# ES_Daisy_Patch_Rev8.net
KiCad netlist of a schematic drawn in EAGLE
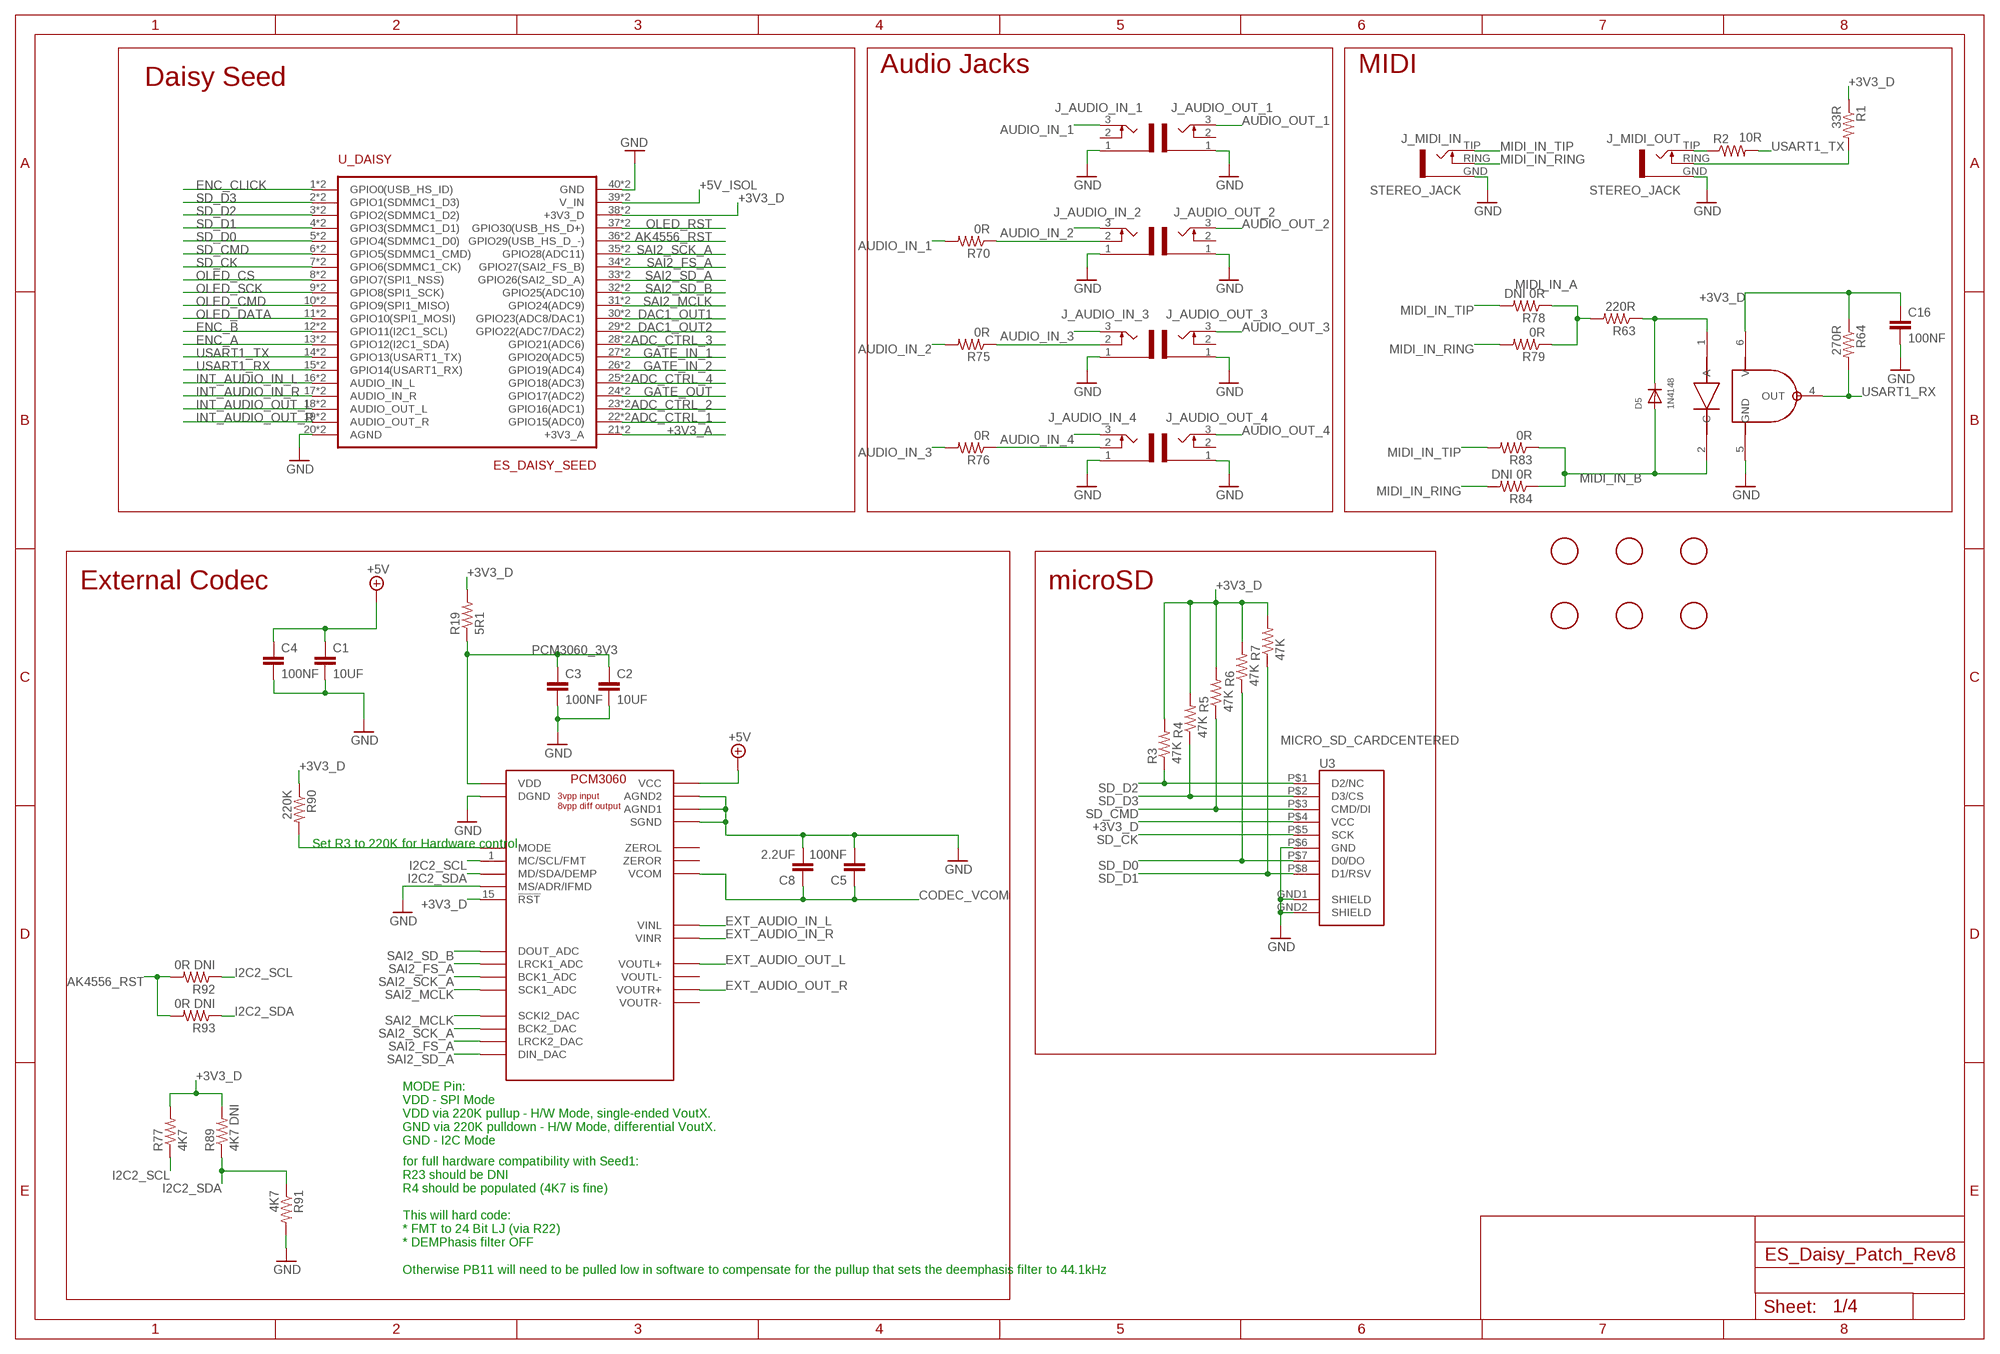
[diagram p0: schematic, sheet 1]
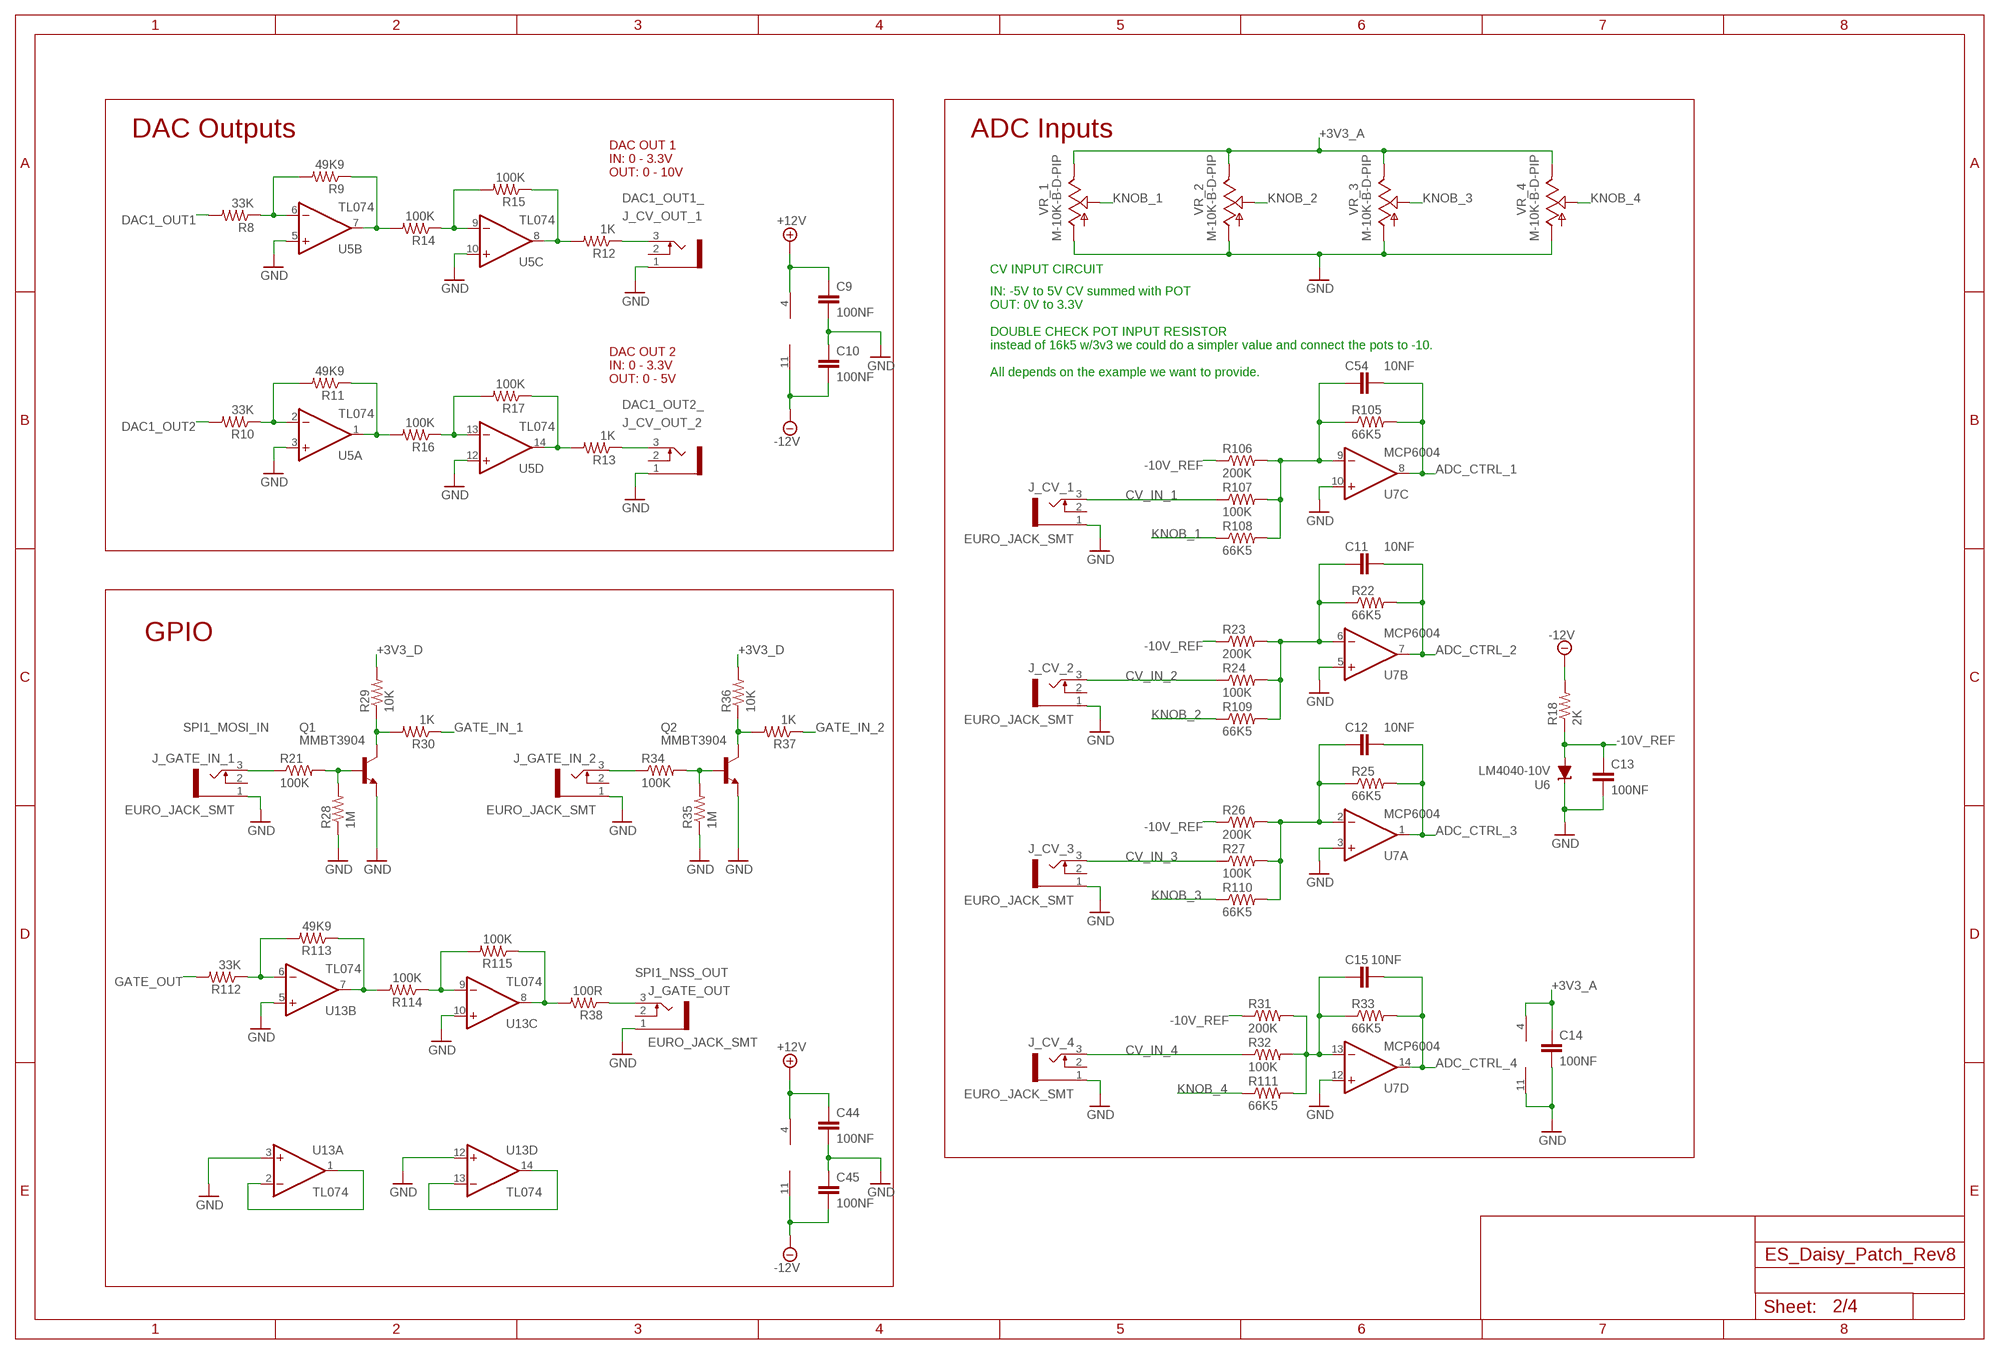
[diagram p1: schematic, sheet 2]
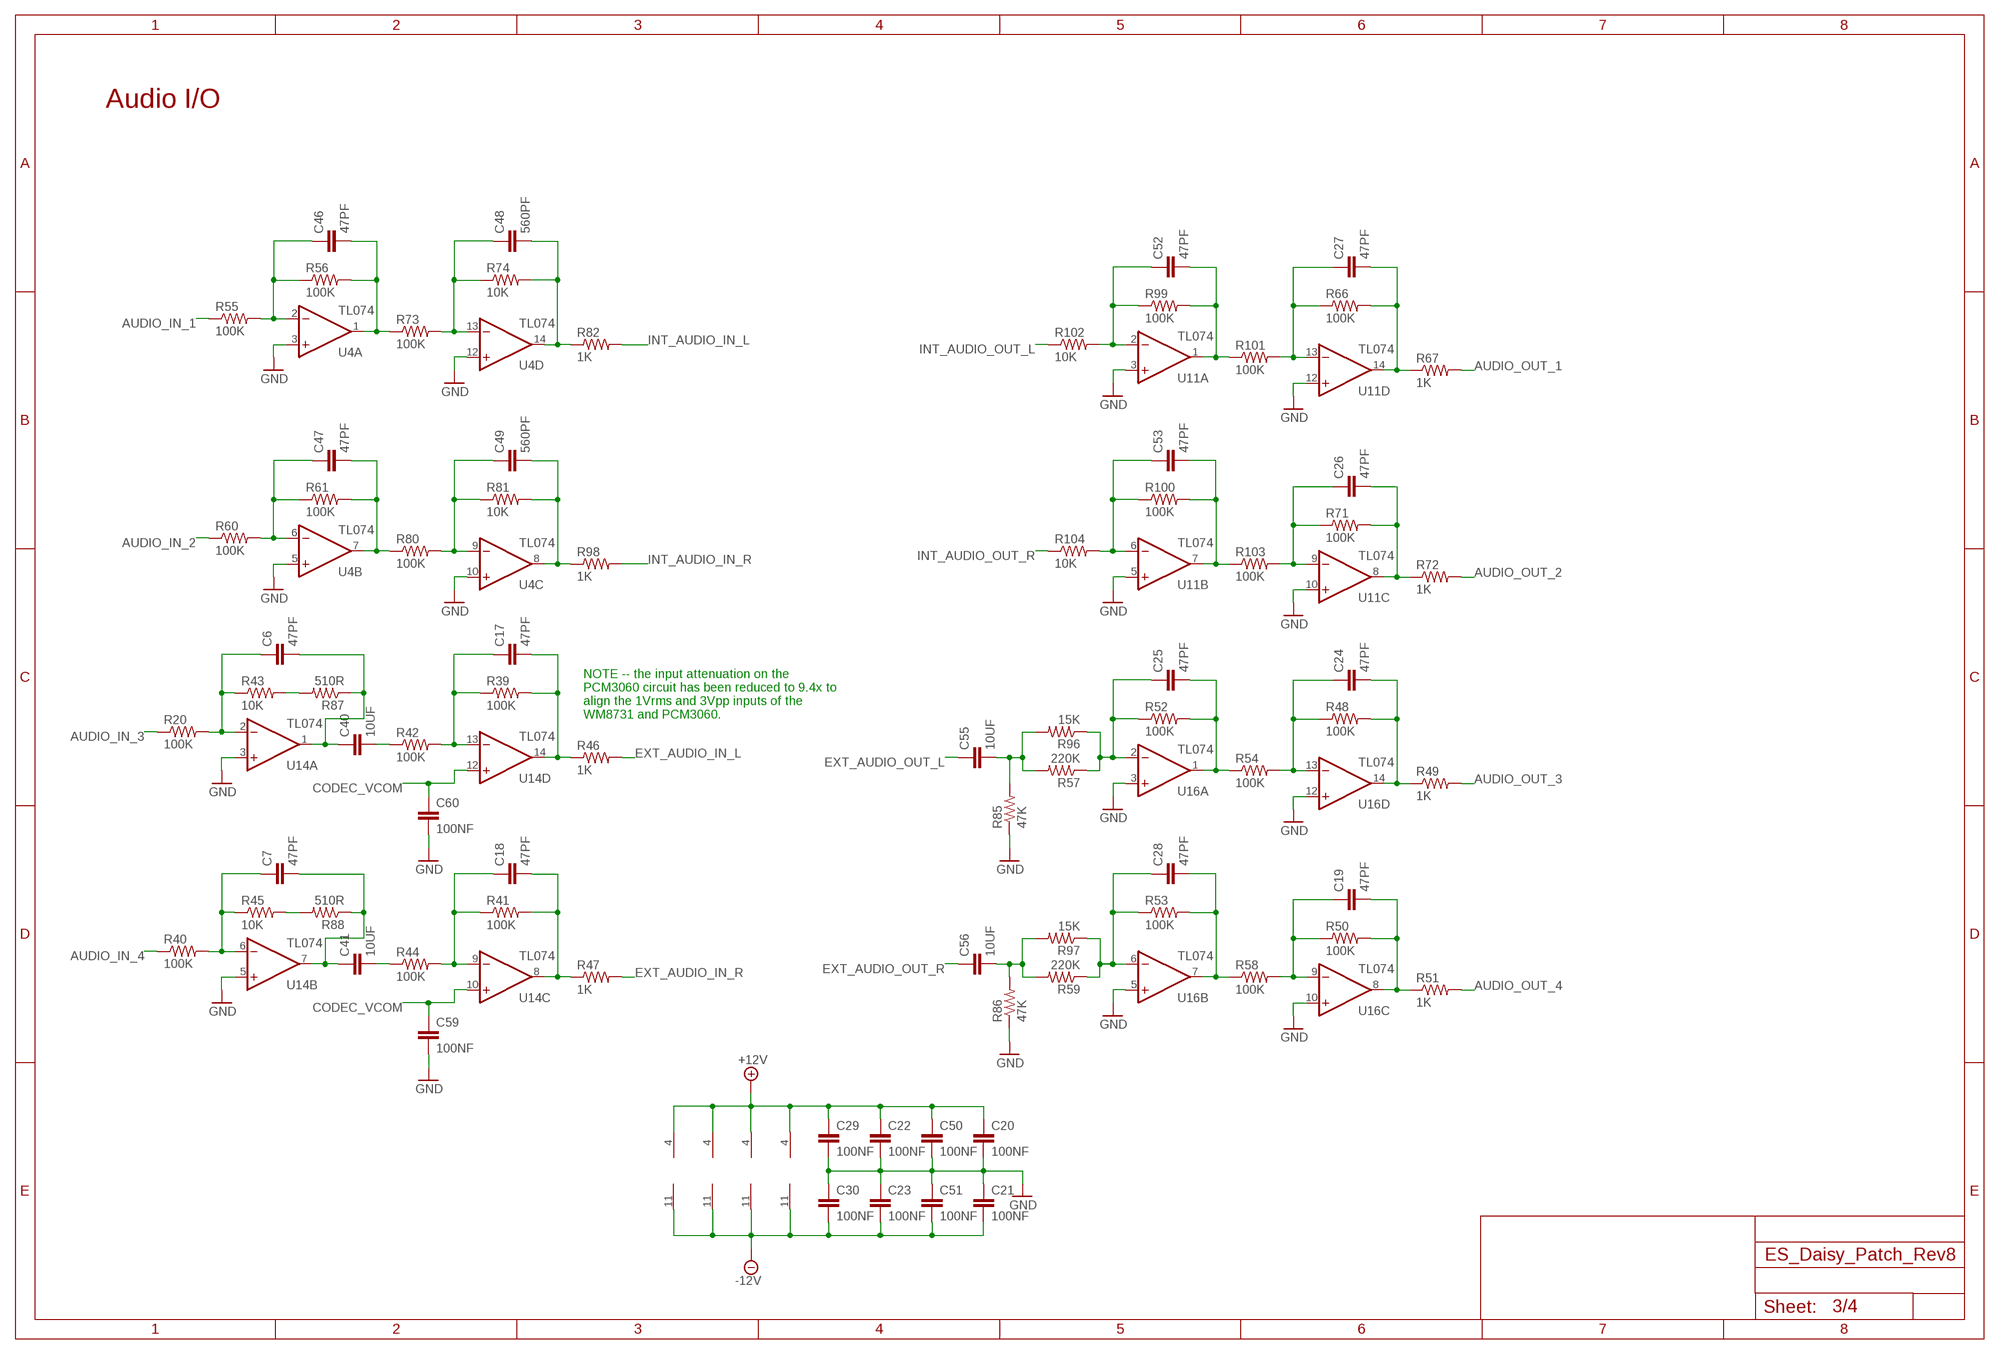
[diagram p2: schematic, sheet 3]
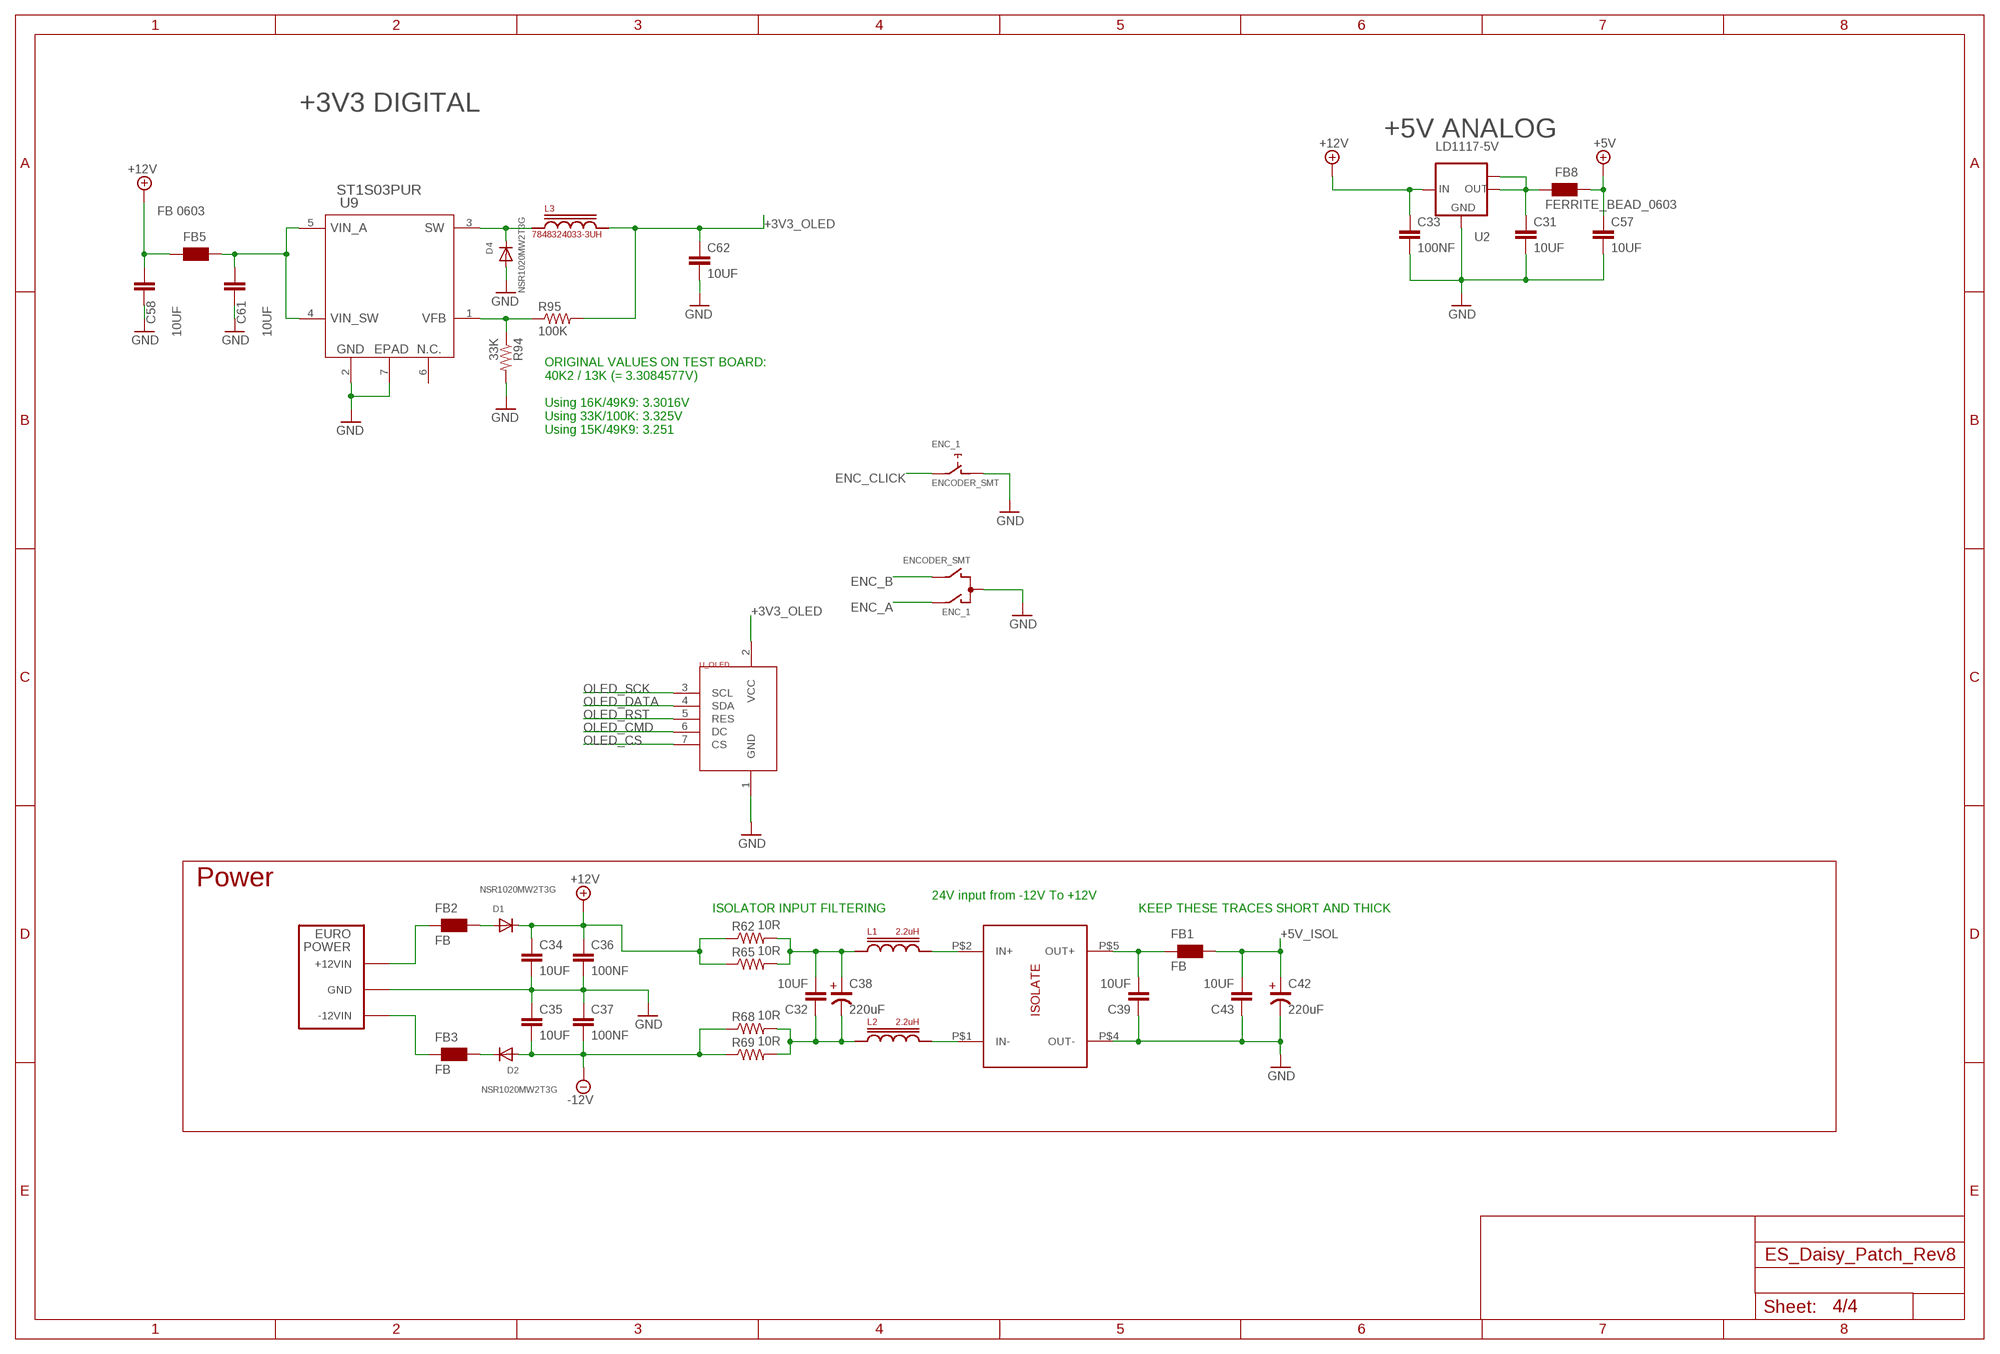
[diagram p3: schematic, sheet 4]

(export (version "E")
  (design (tool "Eeschema 10.0.6"))
  (components
    (comp (ref "C9")
      (value "100NF")
      (footprint "eagle-import:C0402")
      (libsource (lib "eagle-import") (part "C-EUC0402"))
    )
    (comp (ref "C10")
      (value "100NF")
      (footprint "eagle-import:C0402")
      (libsource (lib "eagle-import") (part "C-EUC0402"))
    )
    (comp (ref "C11")
      (value "10NF")
      (footprint "eagle-import:C0603")
      (libsource (lib "eagle-import") (part "C-EUC0603"))
    )
    (comp (ref "C12")
      (value "10NF")
      (footprint "eagle-import:C0603")
      (libsource (lib "eagle-import") (part "C-EUC0603"))
    )
    (comp (ref "C13")
      (value "100NF")
      (footprint "eagle-import:C0402")
      (libsource (lib "eagle-import") (part "C-EUC0402"))
    )
    (comp (ref "C14")
      (value "100NF")
      (footprint "eagle-import:C0402")
      (libsource (lib "eagle-import") (part "C-EUC0402"))
    )
    (comp (ref "C15")
      (value "10NF")
      (footprint "eagle-import:C0603")
      (libsource (lib "eagle-import") (part "C-EUC0603"))
    )
    (comp (ref "C44")
      (value "100NF")
      (footprint "eagle-import:C0402")
      (libsource (lib "eagle-import") (part "C-EUC0402"))
    )
    (comp (ref "C45")
      (value "100NF")
      (footprint "eagle-import:C0402")
      (libsource (lib "eagle-import") (part "C-EUC0402"))
    )
    (comp (ref "C54")
      (value "10NF")
      (footprint "eagle-import:C0603")
      (libsource (lib "eagle-import") (part "C-EUC0603"))
    )
    (comp (ref "J_CV_1")
      (value "EURO_JACK_SMT")
      (footprint "eagle-import:SMT_JACK")
      (libsource (lib "eagle-import") (part "EURO_JACK_SMT"))
    )
    (comp (ref "J_CV_2")
      (value "EURO_JACK_SMT")
      (footprint "eagle-import:SMT_JACK")
      (libsource (lib "eagle-import") (part "EURO_JACK_SMT"))
    )
    (comp (ref "J_CV_3")
      (value "EURO_JACK_SMT")
      (footprint "eagle-import:SMT_JACK")
      (libsource (lib "eagle-import") (part "EURO_JACK_SMT"))
    )
    (comp (ref "J_CV_4")
      (value "EURO_JACK_SMT")
      (footprint "eagle-import:SMT_JACK")
      (libsource (lib "eagle-import") (part "EURO_JACK_SMT"))
    )
    (comp (ref "J_CV_OUT_1")
      (value "EURO_JACK_SMT")
      (footprint "eagle-import:SMT_JACK")
      (libsource (lib "eagle-import") (part "EURO_JACK_SMT"))
    )
    (comp (ref "J_CV_OUT_2")
      (value "EURO_JACK_SMT")
      (footprint "eagle-import:SMT_JACK")
      (libsource (lib "eagle-import") (part "EURO_JACK_SMT"))
    )
    (comp (ref "J_GATE_IN_1")
      (value "EURO_JACK_SMT")
      (footprint "eagle-import:SMT_JACK")
      (libsource (lib "eagle-import") (part "EURO_JACK_SMT"))
    )
    (comp (ref "J_GATE_IN_2")
      (value "EURO_JACK_SMT")
      (footprint "eagle-import:SMT_JACK")
      (libsource (lib "eagle-import") (part "EURO_JACK_SMT"))
    )
    (comp (ref "J_GATE_OUT")
      (value "EURO_JACK_SMT")
      (footprint "eagle-import:SMT_JACK")
      (libsource (lib "eagle-import") (part "EURO_JACK_SMT"))
    )
    (comp (ref "Q1")
      (value "MMBT3904")
      (footprint "eagle-import:SOT23-BEC")
      (libsource (lib "eagle-import") (part "NPNSOT23-BEC"))
    )
    (comp (ref "Q2")
      (value "MMBT3904")
      (footprint "eagle-import:SOT23-BEC")
      (libsource (lib "eagle-import") (part "NPNSOT23-BEC"))
    )
    (comp (ref "R8")
      (value "33K")
      (footprint "eagle-import:R0603")
      (libsource (lib "eagle-import") (part "R-US_R0603"))
    )
    (comp (ref "R9")
      (value "49K9")
      (footprint "eagle-import:R0603")
      (libsource (lib "eagle-import") (part "R-US_R0603"))
    )
    (comp (ref "R10")
      (value "33K")
      (footprint "eagle-import:R0603")
      (libsource (lib "eagle-import") (part "R-US_R0603"))
    )
    (comp (ref "R11")
      (value "49K9")
      (footprint "eagle-import:R0603")
      (libsource (lib "eagle-import") (part "R-US_R0603"))
    )
    (comp (ref "R12")
      (value "1K")
      (footprint "eagle-import:R0402")
      (libsource (lib "eagle-import") (part "R-US_R0402"))
    )
    (comp (ref "R13")
      (value "1K")
      (footprint "eagle-import:R0402")
      (libsource (lib "eagle-import") (part "R-US_R0402"))
    )
    (comp (ref "R14")
      (value "100K")
      (footprint "eagle-import:R0402")
      (libsource (lib "eagle-import") (part "R-US_R0402"))
    )
    (comp (ref "R15")
      (value "100K")
      (footprint "eagle-import:R0402")
      (libsource (lib "eagle-import") (part "R-US_R0402"))
    )
    (comp (ref "R16")
      (value "100K")
      (footprint "eagle-import:R0402")
      (libsource (lib "eagle-import") (part "R-US_R0402"))
    )
    (comp (ref "R17")
      (value "100K")
      (footprint "eagle-import:R0402")
      (libsource (lib "eagle-import") (part "R-US_R0402"))
    )
    (comp (ref "R18")
      (value "2K")
      (footprint "eagle-import:R0603")
      (libsource (lib "eagle-import") (part "R-US_R0603"))
    )
    (comp (ref "R21")
      (value "100K")
      (footprint "eagle-import:R0402")
      (libsource (lib "eagle-import") (part "R-US_R0402"))
    )
    (comp (ref "R22")
      (value "66K5")
      (footprint "eagle-import:R0603")
      (libsource (lib "eagle-import") (part "R-US_R0603"))
    )
    (comp (ref "R23")
      (value "200K")
      (footprint "eagle-import:R0603")
      (libsource (lib "eagle-import") (part "R-US_R0603"))
    )
    (comp (ref "R24")
      (value "100K")
      (footprint "eagle-import:R0402")
      (libsource (lib "eagle-import") (part "R-US_R0402"))
    )
    (comp (ref "R25")
      (value "66K5")
      (footprint "eagle-import:R0603")
      (libsource (lib "eagle-import") (part "R-US_R0603"))
    )
    (comp (ref "R26")
      (value "200K")
      (footprint "eagle-import:R0603")
      (libsource (lib "eagle-import") (part "R-US_R0603"))
    )
    (comp (ref "R27")
      (value "100K")
      (footprint "eagle-import:R0402")
      (libsource (lib "eagle-import") (part "R-US_R0402"))
    )
    (comp (ref "R28")
      (value "1M")
      (footprint "eagle-import:R0603")
      (libsource (lib "eagle-import") (part "R-US_R0603"))
    )
    (comp (ref "R29")
      (value "10K")
      (footprint "eagle-import:R0603")
      (libsource (lib "eagle-import") (part "R-US_R0603"))
    )
    (comp (ref "R30")
      (value "1K")
      (footprint "eagle-import:R0402")
      (libsource (lib "eagle-import") (part "R-US_R0402"))
    )
    (comp (ref "R31")
      (value "200K")
      (footprint "eagle-import:R0603")
      (libsource (lib "eagle-import") (part "R-US_R0603"))
    )
    (comp (ref "R32")
      (value "100K")
      (footprint "eagle-import:R0402")
      (libsource (lib "eagle-import") (part "R-US_R0402"))
    )
    (comp (ref "R33")
      (value "66K5")
      (footprint "eagle-import:R0603")
      (libsource (lib "eagle-import") (part "R-US_R0603"))
    )
    (comp (ref "R34")
      (value "100K")
      (footprint "eagle-import:R0402")
      (libsource (lib "eagle-import") (part "R-US_R0402"))
    )
    (comp (ref "R35")
      (value "1M")
      (footprint "eagle-import:R0603")
      (libsource (lib "eagle-import") (part "R-US_R0603"))
    )
    (comp (ref "R36")
      (value "10K")
      (footprint "eagle-import:R0603")
      (libsource (lib "eagle-import") (part "R-US_R0603"))
    )
    (comp (ref "R37")
      (value "1K")
      (footprint "eagle-import:R0402")
      (libsource (lib "eagle-import") (part "R-US_R0402"))
    )
    (comp (ref "R38")
      (value "100R")
      (footprint "eagle-import:R0603")
      (libsource (lib "eagle-import") (part "R-US_R0603"))
    )
    (comp (ref "R105")
      (value "66K5")
      (footprint "eagle-import:R0603")
      (libsource (lib "eagle-import") (part "R-US_R0603"))
    )
    (comp (ref "R106")
      (value "200K")
      (footprint "eagle-import:R0603")
      (libsource (lib "eagle-import") (part "R-US_R0603"))
    )
    (comp (ref "R107")
      (value "100K")
      (footprint "eagle-import:R0402")
      (libsource (lib "eagle-import") (part "R-US_R0402"))
    )
    (comp (ref "R108")
      (value "66K5")
      (footprint "eagle-import:R0603")
      (libsource (lib "eagle-import") (part "R-US_R0603"))
    )
    (comp (ref "R109")
      (value "66K5")
      (footprint "eagle-import:R0603")
      (libsource (lib "eagle-import") (part "R-US_R0603"))
    )
    (comp (ref "R110")
      (value "66K5")
      (footprint "eagle-import:R0603")
      (libsource (lib "eagle-import") (part "R-US_R0603"))
    )
    (comp (ref "R111")
      (value "66K5")
      (footprint "eagle-import:R0603")
      (libsource (lib "eagle-import") (part "R-US_R0603"))
    )
    (comp (ref "R112")
      (value "33K")
      (footprint "eagle-import:R0603")
      (libsource (lib "eagle-import") (part "R-US_R0603"))
    )
    (comp (ref "R113")
      (value "49K9")
      (footprint "eagle-import:R0603")
      (libsource (lib "eagle-import") (part "R-US_R0603"))
    )
    (comp (ref "R114")
      (value "100K")
      (footprint "eagle-import:R0402")
      (libsource (lib "eagle-import") (part "R-US_R0402"))
    )
    (comp (ref "R115")
      (value "100K")
      (footprint "eagle-import:R0402")
      (libsource (lib "eagle-import") (part "R-US_R0402"))
    )
    (comp (ref "U5")
      (value "TL074")
      (footprint "eagle-import:TSSOP-14")
      (fields (field (name "MPN") "TL074CPWR"))
      (libsource (lib "eagle-import") (part "TL074_TSSOP-14"))
    )
    (comp (ref "U6")
      (value "LM4040-10V")
      (footprint "eagle-import:DBZ_R-PDSO-G3")
      (fields (field (name "MPN") "LM4041A12IDBZR"))
      (libsource (lib "eagle-import") (part "LM4040-10VDBZA12"))
    )
    (comp (ref "U7")
      (value "MCP6004")
      (footprint "eagle-import:TSSOP-14")
      (fields (field (name "MPN") "MCP6004T-E/ST"))
      (libsource (lib "eagle-import") (part "MCP6004_TSSOP-14"))
    )
    (comp (ref "U13")
      (value "TL074")
      (footprint "eagle-import:TSSOP-14")
      (fields (field (name "MPN") "TL074CPWR"))
      (libsource (lib "eagle-import") (part "TL074_TSSOP-14"))
    )
    (comp (ref "VR_1")
      (value "M-10K-B-D-PIP")
      (footprint "eagle-import:PIP_POT_PASTE6")
      (libsource (lib "eagle-import") (part "POT_9MM_SNAP-IN__PIPC6"))
    )
    (comp (ref "VR_2")
      (value "M-10K-B-D-PIP")
      (footprint "eagle-import:PIP_POT_PASTE6")
      (libsource (lib "eagle-import") (part "POT_9MM_SNAP-IN__PIPC6"))
    )
    (comp (ref "VR_3")
      (value "M-10K-B-D-PIP")
      (footprint "eagle-import:PIP_POT_PASTE6")
      (libsource (lib "eagle-import") (part "POT_9MM_SNAP-IN__PIPC6"))
    )
    (comp (ref "VR_4")
      (value "M-10K-B-D-PIP")
      (footprint "eagle-import:PIP_POT_PASTE6")
      (libsource (lib "eagle-import") (part "POT_9MM_SNAP-IN__PIPC6"))
    )
    (comp (ref "C6")
      (value "47PF")
      (footprint "eagle-import:C0603")
      (libsource (lib "eagle-import") (part "C-EUC0603"))
    )
    (comp (ref "C7")
      (value "47PF")
      (footprint "eagle-import:C0603")
      (libsource (lib "eagle-import") (part "C-EUC0603"))
    )
    (comp (ref "C17")
      (value "47PF")
      (footprint "eagle-import:C0603")
      (libsource (lib "eagle-import") (part "C-EUC0603"))
    )
    (comp (ref "C18")
      (value "47PF")
      (footprint "eagle-import:C0603")
      (libsource (lib "eagle-import") (part "C-EUC0603"))
    )
    (comp (ref "C19")
      (value "47PF")
      (footprint "eagle-import:C0603")
      (libsource (lib "eagle-import") (part "C-EUC0603"))
    )
    (comp (ref "C20")
      (value "100NF")
      (footprint "eagle-import:C0402")
      (libsource (lib "eagle-import") (part "C-EUC0402"))
    )
    (comp (ref "C21")
      (value "100NF")
      (footprint "eagle-import:C0402")
      (libsource (lib "eagle-import") (part "C-EUC0402"))
    )
    (comp (ref "C22")
      (value "100NF")
      (footprint "eagle-import:C0402")
      (libsource (lib "eagle-import") (part "C-EUC0402"))
    )
    (comp (ref "C23")
      (value "100NF")
      (footprint "eagle-import:C0402")
      (libsource (lib "eagle-import") (part "C-EUC0402"))
    )
    (comp (ref "C24")
      (value "47PF")
      (footprint "eagle-import:C0603")
      (libsource (lib "eagle-import") (part "C-EUC0603"))
    )
    (comp (ref "C25")
      (value "47PF")
      (footprint "eagle-import:C0603")
      (libsource (lib "eagle-import") (part "C-EUC0603"))
    )
    (comp (ref "C26")
      (value "47PF")
      (footprint "eagle-import:C0603")
      (libsource (lib "eagle-import") (part "C-EUC0603"))
    )
    (comp (ref "C27")
      (value "47PF")
      (footprint "eagle-import:C0603")
      (libsource (lib "eagle-import") (part "C-EUC0603"))
    )
    (comp (ref "C28")
      (value "47PF")
      (footprint "eagle-import:C0603")
      (libsource (lib "eagle-import") (part "C-EUC0603"))
    )
    (comp (ref "C29")
      (value "100NF")
      (footprint "eagle-import:C0402")
      (libsource (lib "eagle-import") (part "C-EUC0402"))
    )
    (comp (ref "C30")
      (value "100NF")
      (footprint "eagle-import:C0402")
      (libsource (lib "eagle-import") (part "C-EUC0402"))
    )
    (comp (ref "C40")
      (value "10UF")
      (footprint "eagle-import:C0805")
      (libsource (lib "eagle-import") (part "C-EUC0805"))
    )
    (comp (ref "C41")
      (value "10UF")
      (footprint "eagle-import:C0805")
      (libsource (lib "eagle-import") (part "C-EUC0805"))
    )
    (comp (ref "C46")
      (value "47PF")
      (footprint "eagle-import:C0603")
      (libsource (lib "eagle-import") (part "C-EUC0603"))
    )
    (comp (ref "C47")
      (value "47PF")
      (footprint "eagle-import:C0603")
      (libsource (lib "eagle-import") (part "C-EUC0603"))
    )
    (comp (ref "C48")
      (value "560PF")
      (footprint "eagle-import:C0603")
      (libsource (lib "eagle-import") (part "C-EUC0603"))
    )
    (comp (ref "C49")
      (value "560PF")
      (footprint "eagle-import:C0603")
      (libsource (lib "eagle-import") (part "C-EUC0603"))
    )
    (comp (ref "C50")
      (value "100NF")
      (footprint "eagle-import:C0402")
      (libsource (lib "eagle-import") (part "C-EUC0402"))
    )
    (comp (ref "C51")
      (value "100NF")
      (footprint "eagle-import:C0402")
      (libsource (lib "eagle-import") (part "C-EUC0402"))
    )
    (comp (ref "C52")
      (value "47PF")
      (footprint "eagle-import:C0603")
      (libsource (lib "eagle-import") (part "C-EUC0603"))
    )
    (comp (ref "C53")
      (value "47PF")
      (footprint "eagle-import:C0603")
      (libsource (lib "eagle-import") (part "C-EUC0603"))
    )
    (comp (ref "C55")
      (value "10UF")
      (footprint "eagle-import:C0805")
      (libsource (lib "eagle-import") (part "C-EUC0805"))
    )
    (comp (ref "C56")
      (value "10UF")
      (footprint "eagle-import:C0805")
      (libsource (lib "eagle-import") (part "C-EUC0805"))
    )
    (comp (ref "C59")
      (value "100NF")
      (footprint "eagle-import:C0402")
      (libsource (lib "eagle-import") (part "C-EUC0402"))
    )
    (comp (ref "C60")
      (value "100NF")
      (footprint "eagle-import:C0402")
      (libsource (lib "eagle-import") (part "C-EUC0402"))
    )
    (comp (ref "R20")
      (value "100K")
      (footprint "eagle-import:R0402")
      (libsource (lib "eagle-import") (part "R-US_R0402"))
    )
    (comp (ref "R39")
      (value "100K")
      (footprint "eagle-import:R0402")
      (libsource (lib "eagle-import") (part "R-US_R0402"))
    )
    (comp (ref "R40")
      (value "100K")
      (footprint "eagle-import:R0402")
      (libsource (lib "eagle-import") (part "R-US_R0402"))
    )
    (comp (ref "R41")
      (value "100K")
      (footprint "eagle-import:R0402")
      (libsource (lib "eagle-import") (part "R-US_R0402"))
    )
    (comp (ref "R42")
      (value "100K")
      (footprint "eagle-import:R0402")
      (libsource (lib "eagle-import") (part "R-US_R0402"))
    )
    (comp (ref "R43")
      (value "10K")
      (footprint "eagle-import:R0603")
      (libsource (lib "eagle-import") (part "R-US_R0603"))
    )
    (comp (ref "R44")
      (value "100K")
      (footprint "eagle-import:R0402")
      (libsource (lib "eagle-import") (part "R-US_R0402"))
    )
    (comp (ref "R45")
      (value "10K")
      (footprint "eagle-import:R0603")
      (libsource (lib "eagle-import") (part "R-US_R0603"))
    )
    (comp (ref "R46")
      (value "1K")
      (footprint "eagle-import:R0402")
      (libsource (lib "eagle-import") (part "R-US_R0402"))
    )
    (comp (ref "R47")
      (value "1K")
      (footprint "eagle-import:R0402")
      (libsource (lib "eagle-import") (part "R-US_R0402"))
    )
    (comp (ref "R48")
      (value "100K")
      (footprint "eagle-import:R0402")
      (libsource (lib "eagle-import") (part "R-US_R0402"))
    )
    (comp (ref "R49")
      (value "1K")
      (footprint "eagle-import:R0402")
      (libsource (lib "eagle-import") (part "R-US_R0402"))
    )
    (comp (ref "R50")
      (value "100K")
      (footprint "eagle-import:R0402")
      (libsource (lib "eagle-import") (part "R-US_R0402"))
    )
    (comp (ref "R51")
      (value "1K")
      (footprint "eagle-import:R0402")
      (libsource (lib "eagle-import") (part "R-US_R0402"))
    )
    (comp (ref "R52")
      (value "100K")
      (footprint "eagle-import:R0402")
      (libsource (lib "eagle-import") (part "R-US_R0402"))
    )
    (comp (ref "R53")
      (value "100K")
      (footprint "eagle-import:R0402")
      (libsource (lib "eagle-import") (part "R-US_R0402"))
    )
    (comp (ref "R54")
      (value "100K")
      (footprint "eagle-import:R0402")
      (libsource (lib "eagle-import") (part "R-US_R0402"))
    )
    (comp (ref "R55")
      (value "100K")
      (footprint "eagle-import:R0402")
      (libsource (lib "eagle-import") (part "R-US_R0402"))
    )
    (comp (ref "R56")
      (value "100K")
      (footprint "eagle-import:R0402")
      (libsource (lib "eagle-import") (part "R-US_R0402"))
    )
    (comp (ref "R57")
      (value "220K")
      (footprint "eagle-import:R0603")
      (libsource (lib "eagle-import") (part "R-US_R0603"))
    )
    (comp (ref "R58")
      (value "100K")
      (footprint "eagle-import:R0402")
      (libsource (lib "eagle-import") (part "R-US_R0402"))
    )
    (comp (ref "R59")
      (value "220K")
      (footprint "eagle-import:R0603")
      (libsource (lib "eagle-import") (part "R-US_R0603"))
    )
    (comp (ref "R60")
      (value "100K")
      (footprint "eagle-import:R0402")
      (libsource (lib "eagle-import") (part "R-US_R0402"))
    )
    (comp (ref "R61")
      (value "100K")
      (footprint "eagle-import:R0402")
      (libsource (lib "eagle-import") (part "R-US_R0402"))
    )
    (comp (ref "R66")
      (value "100K")
      (footprint "eagle-import:R0402")
      (libsource (lib "eagle-import") (part "R-US_R0402"))
    )
    (comp (ref "R67")
      (value "1K")
      (footprint "eagle-import:R0402")
      (libsource (lib "eagle-import") (part "R-US_R0402"))
    )
    (comp (ref "R71")
      (value "100K")
      (footprint "eagle-import:R0402")
      (libsource (lib "eagle-import") (part "R-US_R0402"))
    )
    (comp (ref "R72")
      (value "1K")
      (footprint "eagle-import:R0402")
      (libsource (lib "eagle-import") (part "R-US_R0402"))
    )
    (comp (ref "R73")
      (value "100K")
      (footprint "eagle-import:R0402")
      (libsource (lib "eagle-import") (part "R-US_R0402"))
    )
    (comp (ref "R74")
      (value "10K")
      (footprint "eagle-import:R0603")
      (libsource (lib "eagle-import") (part "R-US_R0603"))
    )
    (comp (ref "R80")
      (value "100K")
      (footprint "eagle-import:R0402")
      (libsource (lib "eagle-import") (part "R-US_R0402"))
    )
    (comp (ref "R81")
      (value "10K")
      (footprint "eagle-import:R0603")
      (libsource (lib "eagle-import") (part "R-US_R0603"))
    )
    (comp (ref "R82")
      (value "1K")
      (footprint "eagle-import:R0402")
      (libsource (lib "eagle-import") (part "R-US_R0402"))
    )
    (comp (ref "R85")
      (value "47K")
      (footprint "eagle-import:R0603")
      (libsource (lib "eagle-import") (part "R-US_R0603"))
    )
    (comp (ref "R86")
      (value "47K")
      (footprint "eagle-import:R0603")
      (libsource (lib "eagle-import") (part "R-US_R0603"))
    )
    (comp (ref "R87")
      (value "510R")
      (footprint "eagle-import:R0603")
      (libsource (lib "eagle-import") (part "R-US_R0603"))
    )
    (comp (ref "R88")
      (value "510R")
      (footprint "eagle-import:R0603")
      (libsource (lib "eagle-import") (part "R-US_R0603"))
    )
    (comp (ref "R96")
      (value "15K")
      (footprint "eagle-import:R0603")
      (libsource (lib "eagle-import") (part "R-US_R0603"))
    )
    (comp (ref "R97")
      (value "15K")
      (footprint "eagle-import:R0603")
      (libsource (lib "eagle-import") (part "R-US_R0603"))
    )
    (comp (ref "R98")
      (value "1K")
      (footprint "eagle-import:R0402")
      (libsource (lib "eagle-import") (part "R-US_R0402"))
    )
    (comp (ref "R99")
      (value "100K")
      (footprint "eagle-import:R0402")
      (libsource (lib "eagle-import") (part "R-US_R0402"))
    )
    (comp (ref "R100")
      (value "100K")
      (footprint "eagle-import:R0402")
      (libsource (lib "eagle-import") (part "R-US_R0402"))
    )
    (comp (ref "R101")
      (value "100K")
      (footprint "eagle-import:R0402")
      (libsource (lib "eagle-import") (part "R-US_R0402"))
    )
    (comp (ref "R102")
      (value "10K")
      (footprint "eagle-import:R0603")
      (libsource (lib "eagle-import") (part "R-US_R0603"))
    )
    (comp (ref "R103")
      (value "100K")
      (footprint "eagle-import:R0402")
      (libsource (lib "eagle-import") (part "R-US_R0402"))
    )
    (comp (ref "R104")
      (value "10K")
      (footprint "eagle-import:R0603")
      (libsource (lib "eagle-import") (part "R-US_R0603"))
    )
    (comp (ref "U4")
      (value "TL074")
      (footprint "eagle-import:TSSOP-14")
      (fields (field (name "MPN") "TL074CPWR"))
      (libsource (lib "eagle-import") (part "TL074_TSSOP-14"))
    )
    (comp (ref "U11")
      (value "TL074")
      (footprint "eagle-import:TSSOP-14")
      (fields (field (name "MPN") "TL074CPWR"))
      (libsource (lib "eagle-import") (part "TL074_TSSOP-14"))
    )
    (comp (ref "U14")
      (value "TL074")
      (footprint "eagle-import:TSSOP-14")
      (fields (field (name "MPN") "TL074CPWR"))
      (libsource (lib "eagle-import") (part "TL074_TSSOP-14"))
    )
    (comp (ref "U16")
      (value "TL074")
      (footprint "eagle-import:TSSOP-14")
      (fields (field (name "MPN") "TL074CPWR"))
      (libsource (lib "eagle-import") (part "TL074_TSSOP-14"))
    )
    (comp (ref "C31")
      (value "10UF")
      (footprint "eagle-import:C0805")
      (libsource (lib "eagle-import") (part "C-EUC0805"))
    )
    (comp (ref "C32")
      (value "10UF")
      (footprint "eagle-import:C0805")
      (libsource (lib "eagle-import") (part "C-EUC0805"))
    )
    (comp (ref "C33")
      (value "100NF")
      (footprint "eagle-import:C0402")
      (libsource (lib "eagle-import") (part "C-EUC0402"))
    )
    (comp (ref "C34")
      (value "10UF")
      (footprint "eagle-import:C0805")
      (libsource (lib "eagle-import") (part "C-EUC0805"))
    )
    (comp (ref "C35")
      (value "10UF")
      (footprint "eagle-import:C0805")
      (libsource (lib "eagle-import") (part "C-EUC0805"))
    )
    (comp (ref "C36")
      (value "100NF")
      (footprint "eagle-import:C0402")
      (libsource (lib "eagle-import") (part "C-EUC0402"))
    )
    (comp (ref "C37")
      (value "100NF")
      (footprint "eagle-import:C0402")
      (libsource (lib "eagle-import") (part "C-EUC0402"))
    )
    (comp (ref "C38")
      (value "220uF")
      (footprint "eagle-import:PANASONIC_D")
      (libsource (lib "eagle-import") (part "C-EU-POL_D"))
    )
    (comp (ref "C39")
      (value "10UF")
      (footprint "eagle-import:C0805")
      (libsource (lib "eagle-import") (part "C-EUC0805"))
    )
    (comp (ref "C42")
      (value "220uF")
      (footprint "eagle-import:PANASONIC_D")
      (libsource (lib "eagle-import") (part "C-EU-POL_D"))
    )
    (comp (ref "C43")
      (value "10UF")
      (footprint "eagle-import:C0805")
      (libsource (lib "eagle-import") (part "C-EUC0805"))
    )
    (comp (ref "C57")
      (value "10UF")
      (footprint "eagle-import:C0805")
      (libsource (lib "eagle-import") (part "C-EUC0805"))
    )
    (comp (ref "C58")
      (value "10UF")
      (footprint "eagle-import:C0805")
      (libsource (lib "eagle-import") (part "C-EUC0805"))
    )
    (comp (ref "C61")
      (value "10UF")
      (footprint "eagle-import:C0805")
      (libsource (lib "eagle-import") (part "Electrosmith-Passives_29888544_C-EUC0805"))
    )
    (comp (ref "C62")
      (value "10UF")
      (footprint "eagle-import:C0805")
      (libsource (lib "eagle-import") (part "C-EUC0805"))
    )
    (comp (ref "D1")
      (value "NSR1020MW2T3G")
      (footprint "eagle-import:SOD-323F")
      (libsource (lib "eagle-import") (part "DIODE_SOD-323F"))
    )
    (comp (ref "D2")
      (value "NSR1020MW2T3G")
      (footprint "eagle-import:SOD-323F")
      (libsource (lib "eagle-import") (part "DIODE_SOD-323F"))
    )
    (comp (ref "D4")
      (value "NSR1020MW2T3G")
      (footprint "eagle-import:SOD-323F")
      (libsource (lib "eagle-import") (part "Electrosmith-Semiconductors_29887508_DIODE_SOD-323F"))
    )
    (comp (ref "ENC_1")
      (value "ENCODER_SMT")
      (footprint "eagle-import:VH1-147")
      (libsource (lib "eagle-import") (part "ENCODER_SMT"))
    )
    (comp (ref "EP1")
      (value "EURORACK_POWERSMT_2X8")
      (footprint "eagle-import:2X8_SMD_PWR")
      (libsource (lib "eagle-import") (part "EURORACK_POWERSMT_2X8"))
    )
    (comp (ref "FB1")
      (value "FB")
      (footprint "eagle-import:WUERTH-ELEKTRONIK_0603")
      (fields (field (name "MPN") "MI0603J601R-10"))
      (libsource (lib "eagle-import") (part "FERRITE_BEAD_0603"))
    )
    (comp (ref "FB2")
      (value "FB")
      (footprint "eagle-import:WUERTH-ELEKTRONIK_0603")
      (fields (field (name "MPN") "MI0603J601R-10"))
      (libsource (lib "eagle-import") (part "FERRITE_BEAD_0603"))
    )
    (comp (ref "FB3")
      (value "FB")
      (footprint "eagle-import:WUERTH-ELEKTRONIK_0603")
      (fields (field (name "MPN") "MI0603J601R-10"))
      (libsource (lib "eagle-import") (part "FERRITE_BEAD_0603"))
    )
    (comp (ref "FB5")
      (value "FB 0603")
      (footprint "eagle-import:WUERTH-ELEKTRONIK_0603")
      (fields (field (name "MPN") "MI0603J601R-10"))
      (libsource (lib "eagle-import") (part "FERRITE_BEAD_0603"))
    )
    (comp (ref "FB8")
      (value "FERRITE_BEAD_0603")
      (footprint "eagle-import:WUERTH-ELEKTRONIK_0603")
      (fields (field (name "MPN") "MI0603J601R-10"))
      (libsource (lib "eagle-import") (part "FERRITE_BEAD_0603"))
    )
    (comp (ref "L1")
      (value "2.2uH")
      (footprint "eagle-import:BOURNS_SRP2010")
      (libsource (lib "eagle-import") (part "INDUCTORS"))
    )
    (comp (ref "L2")
      (value "2.2uH")
      (footprint "eagle-import:BOURNS_SRP2010")
      (libsource (lib "eagle-import") (part "INDUCTORS"))
    )
    (comp (ref "L3")
      (value "7848324033-3UH")
      (footprint "eagle-import:I1008")
      (fields (field (name "MPN") "AIML-1008HC-3R3M-T"))
      (libsource (lib "eagle-import") (part "INDUCTOR1008"))
    )
    (comp (ref "R62")
      (value "10R")
      (footprint "eagle-import:R0603")
      (libsource (lib "eagle-import") (part "R-US_R0603"))
    )
    (comp (ref "R65")
      (value "10R")
      (footprint "eagle-import:R0603")
      (libsource (lib "eagle-import") (part "R-US_R0603"))
    )
    (comp (ref "R68")
      (value "10R")
      (footprint "eagle-import:R0603")
      (libsource (lib "eagle-import") (part "R-US_R0603"))
    )
    (comp (ref "R69")
      (value "10R")
      (footprint "eagle-import:R0603")
      (libsource (lib "eagle-import") (part "R-US_R0603"))
    )
    (comp (ref "R94")
      (value "33K")
      (footprint "eagle-import:R0603")
      (libsource (lib "eagle-import") (part "R-US_R0603"))
    )
    (comp (ref "R95")
      (value "100K")
      (footprint "eagle-import:R0402")
      (libsource (lib "eagle-import") (part "R-US_R0402"))
    )
    (comp (ref "U$1")
      (value "U24V/5V DC/DC ISOLATOR")
      (footprint "eagle-import:XP_POWER_ISEXXXXA")
      (fields (field (name "MPN") "ISE2405A"))
      (libsource (lib "eagle-import") (part "POWER_ISOLATE"))
    )
    (comp (ref "U2")
      (value "LD1117-5V")
      (footprint "eagle-import:SOT223")
      (fields (field (name "MPN") "LD1117S50CTR"))
      (libsource (lib "eagle-import") (part "LD1117-5V"))
    )
    (comp (ref "U9")
      (value "ST1S03PUR")
      (footprint "eagle-import:DFN06_3X3_STM")
      (fields (field (name "COPYRIGHT") "Copyright (C) 2021 Ultra Librarian. All rights reserved."))
      (libsource (lib "eagle-import") (part "ST1S03PUR"))
    )
    (comp (ref "U_OLED")
      (value "OLED_DISPLAY")
      (footprint "eagle-import:ER-OLEDM015-2")
      (fields (field (name "MPN") "ER-OLEDM015-2W-SPI-I2C"))
      (libsource (lib "eagle-import") (part "OLED_DISPLAY"))
    )
    (comp (ref "C1")
      (value "10UF")
      (footprint "eagle-import:C0805")
      (libsource (lib "eagle-import") (part "C-EUC0805"))
    )
    (comp (ref "C2")
      (value "10UF")
      (footprint "eagle-import:C0805")
      (libsource (lib "eagle-import") (part "C-EUC0805"))
    )
    (comp (ref "C3")
      (value "100NF")
      (footprint "eagle-import:C0402")
      (libsource (lib "eagle-import") (part "C-EUC0402"))
    )
    (comp (ref "C4")
      (value "100NF")
      (footprint "eagle-import:C0402")
      (libsource (lib "eagle-import") (part "C-EUC0402"))
    )
    (comp (ref "C5")
      (value "100NF")
      (footprint "eagle-import:C0402")
      (libsource (lib "eagle-import") (part "C-EUC0402"))
    )
    (comp (ref "C8")
      (value "2.2UF")
      (footprint "eagle-import:C0603")
      (libsource (lib "eagle-import") (part "C-EUC0603"))
    )
    (comp (ref "C16")
      (value "100NF")
      (footprint "eagle-import:C0402")
      (libsource (lib "eagle-import") (part "C-EUC0402"))
    )
    (comp (ref "D5")
      (value "1N4148")
      (footprint "eagle-import:SOD-323F")
      (libsource (lib "eagle-import") (part "DIODE_SOD-323F"))
    )
    (comp (ref "FD1")
      (value "FIDUCIAL")
      (footprint "eagle-import:FIDUCIAL_1MM")
      (libsource (lib "eagle-import") (part "FIDUCIAL"))
    )
    (comp (ref "FD2")
      (value "FIDUCIAL")
      (footprint "eagle-import:FIDUCIAL_1MM")
      (libsource (lib "eagle-import") (part "FIDUCIAL"))
    )
    (comp (ref "FD3")
      (value "FIDUCIAL")
      (footprint "eagle-import:FIDUCIAL_1MM")
      (libsource (lib "eagle-import") (part "FIDUCIAL"))
    )
    (comp (ref "FD4")
      (value "FIDUCIAL")
      (footprint "eagle-import:FIDUCIAL_1MM")
      (libsource (lib "eagle-import") (part "FIDUCIAL"))
    )
    (comp (ref "FD5")
      (value "FIDUCIAL")
      (footprint "eagle-import:FIDUCIAL_1MM")
      (libsource (lib "eagle-import") (part "FIDUCIAL"))
    )
    (comp (ref "FD6")
      (value "FIDUCIAL")
      (footprint "eagle-import:FIDUCIAL_1MM")
      (libsource (lib "eagle-import") (part "FIDUCIAL"))
    )
    (comp (ref "J_AUDIO_IN_1")
      (value "EURO_JACK_SMT")
      (footprint "eagle-import:SMT_JACK")
      (libsource (lib "eagle-import") (part "EURO_JACK_SMT"))
    )
    (comp (ref "J_AUDIO_IN_2")
      (value "EURO_JACK_SMT")
      (footprint "eagle-import:SMT_JACK")
      (libsource (lib "eagle-import") (part "EURO_JACK_SMT"))
    )
    (comp (ref "J_AUDIO_IN_3")
      (value "EURO_JACK_SMT")
      (footprint "eagle-import:SMT_JACK")
      (libsource (lib "eagle-import") (part "EURO_JACK_SMT"))
    )
    (comp (ref "J_AUDIO_IN_4")
      (value "EURO_JACK_SMT")
      (footprint "eagle-import:SMT_JACK")
      (libsource (lib "eagle-import") (part "EURO_JACK_SMT"))
    )
    (comp (ref "J_AUDIO_OUT_1")
      (value "EURO_JACK_SMT")
      (footprint "eagle-import:SMT_JACK")
      (libsource (lib "eagle-import") (part "EURO_JACK_SMT"))
    )
    (comp (ref "J_AUDIO_OUT_2")
      (value "EURO_JACK_SMT")
      (footprint "eagle-import:SMT_JACK")
      (libsource (lib "eagle-import") (part "EURO_JACK_SMT"))
    )
    (comp (ref "J_AUDIO_OUT_3")
      (value "EURO_JACK_SMT")
      (footprint "eagle-import:SMT_JACK")
      (libsource (lib "eagle-import") (part "EURO_JACK_SMT"))
    )
    (comp (ref "J_AUDIO_OUT_4")
      (value "EURO_JACK_SMT")
      (footprint "eagle-import:SMT_JACK")
      (libsource (lib "eagle-import") (part "EURO_JACK_SMT"))
    )
    (comp (ref "J_MIDI_IN")
      (value "STEREO_JACK")
      (footprint "eagle-import:STEREO_JACK_3.5MM")
      (libsource (lib "eagle-import") (part "STEREO_JACK"))
    )
    (comp (ref "J_MIDI_OUT")
      (value "STEREO_JACK")
      (footprint "eagle-import:STEREO_JACK_3.5MM")
      (libsource (lib "eagle-import") (part "STEREO_JACK"))
    )
    (comp (ref "R1")
      (value "33R")
      (footprint "eagle-import:R0603")
      (libsource (lib "eagle-import") (part "R-US_R0603"))
    )
    (comp (ref "R2")
      (value "10R")
      (footprint "eagle-import:R0603")
      (libsource (lib "eagle-import") (part "R-US_R0603"))
    )
    (comp (ref "R3")
      (value "47K")
      (footprint "eagle-import:R0603")
      (libsource (lib "eagle-import") (part "R-US_R0603"))
    )
    (comp (ref "R4")
      (value "47K")
      (footprint "eagle-import:R0603")
      (libsource (lib "eagle-import") (part "R-US_R0603"))
    )
    (comp (ref "R5")
      (value "47K")
      (footprint "eagle-import:R0603")
      (libsource (lib "eagle-import") (part "R-US_R0603"))
    )
    (comp (ref "R6")
      (value "47K")
      (footprint "eagle-import:R0603")
      (libsource (lib "eagle-import") (part "R-US_R0603"))
    )
    (comp (ref "R7")
      (value "47K")
      (footprint "eagle-import:R0603")
      (libsource (lib "eagle-import") (part "R-US_R0603"))
    )
    (comp (ref "R19")
      (value "5R1")
      (footprint "eagle-import:R0603")
      (libsource (lib "eagle-import") (part "R-US_R0603"))
    )
    (comp (ref "R63")
      (value "220R")
      (footprint "eagle-import:R0603")
      (libsource (lib "eagle-import") (part "R-US_R0603"))
    )
    (comp (ref "R64")
      (value "270R")
      (footprint "eagle-import:R0603")
      (libsource (lib "eagle-import") (part "R-US_R0603"))
    )
    (comp (ref "R70")
      (value "0R")
      (footprint "eagle-import:R0603")
      (libsource (lib "eagle-import") (part "R-US_R0603"))
    )
    (comp (ref "R75")
      (value "0R")
      (footprint "eagle-import:R0603")
      (libsource (lib "eagle-import") (part "R-US_R0603"))
    )
    (comp (ref "R76")
      (value "0R")
      (footprint "eagle-import:R0603")
      (libsource (lib "eagle-import") (part "R-US_R0603"))
    )
    (comp (ref "R77")
      (value "4K7")
      (footprint "eagle-import:R0603")
      (libsource (lib "eagle-import") (part "R-US_R0603"))
    )
    (comp (ref "R78")
      (value "DNI 0R")
      (footprint "eagle-import:R0603")
      (libsource (lib "eagle-import") (part "R-US_R0603"))
    )
    (comp (ref "R79")
      (value "0R")
      (footprint "eagle-import:R0603")
      (libsource (lib "eagle-import") (part "R-US_R0603"))
    )
    (comp (ref "R83")
      (value "0R")
      (footprint "eagle-import:R0603")
      (libsource (lib "eagle-import") (part "R-US_R0603"))
    )
    (comp (ref "R84")
      (value "DNI 0R")
      (footprint "eagle-import:R0603")
      (libsource (lib "eagle-import") (part "R-US_R0603"))
    )
    (comp (ref "R89")
      (value "4K7 DNI")
      (footprint "eagle-import:R0603")
      (libsource (lib "eagle-import") (part "R-US_R0603"))
    )
    (comp (ref "R90")
      (value "220K")
      (footprint "eagle-import:R0603")
      (libsource (lib "eagle-import") (part "R-US_R0603"))
    )
    (comp (ref "R91")
      (value "4K7")
      (footprint "eagle-import:R0603")
      (libsource (lib "eagle-import") (part "R-US_R0603"))
    )
    (comp (ref "R92")
      (value "0R DNI")
      (footprint "eagle-import:R0603")
      (libsource (lib "eagle-import") (part "R-US_R0603"))
    )
    (comp (ref "R93")
      (value "0R DNI")
      (footprint "eagle-import:R0603")
      (libsource (lib "eagle-import") (part "R-US_R0603"))
    )
    (comp (ref "U1")
      (value "PCM3060")
      (footprint "eagle-import:TSSOP-28")
      (libsource (lib "eagle-import") (part "PCM3060PWR"))
    )
    (comp (ref "U3")
      (value "MICRO_SD_CARDCENTERED")
      (footprint "eagle-import:VERT_MICROSD_CENTERED")
      (libsource (lib "eagle-import") (part "MICRO_SD_CARDCENTERED"))
    )
    (comp (ref "U15")
      (value "OPTOISOLATOR_H11L1M")
      (footprint "eagle-import:DIL06_GULLWING")
      (fields (field (name "MPN") "H11L1SR2M"))
      (libsource (lib "eagle-import") (part "OPTOISOLATOR_H11L1M"))
    )
    (comp (ref "U_DAISY")
      (value "ES_DAISY_SEED")
      (footprint "eagle-import:ES_DAISY_SEED_DOUBLE")
      (libsource (lib "eagle-import") (part "ES_DAISY_SEED_REV4_DOUBLE"))
    )
  )
  (nets
    (net (code "1") (name "+3V3_A") (class "Default")
      (node (ref "C14") (pin "1") (pinfunction "1_1") (pintype "passive"))
      (node (ref "U7") (pin "4") (pinfunction "V+_4") (pintype "power_in"))
      (node (ref "U_DAISY") (pin "21") (pinfunction "+3V3_A_21") (pintype "bidirectional"))
      (node (ref "U_DAISY") (pin "B21") (pinfunction "+3V3_A_B21") (pintype "bidirectional"))
      (node (ref "VR_1") (pin "3") (pinfunction "3_3") (pintype "passive"))
      (node (ref "VR_2") (pin "3") (pinfunction "3_3") (pintype "passive"))
      (node (ref "VR_3") (pin "3") (pinfunction "3_3") (pintype "passive"))
      (node (ref "VR_4") (pin "3") (pinfunction "3_3") (pintype "passive"))
    )
    (net (code "2") (name "+3V3_D") (class "Default")
      (node (ref "C16") (pin "1") (pinfunction "1_1") (pintype "passive"))
      (node (ref "R1") (pin "1") (pinfunction "1_1") (pintype "passive"))
      (node (ref "R19") (pin "2") (pinfunction "2_2") (pintype "passive"))
      (node (ref "R29") (pin "2") (pinfunction "2_2") (pintype "passive"))
      (node (ref "R3") (pin "2") (pinfunction "2_2") (pintype "passive"))
      (node (ref "R36") (pin "2") (pinfunction "2_2") (pintype "passive"))
      (node (ref "R4") (pin "2") (pinfunction "2_2") (pintype "passive"))
      (node (ref "R5") (pin "2") (pinfunction "2_2") (pintype "passive"))
      (node (ref "R6") (pin "2") (pinfunction "2_2") (pintype "passive"))
      (node (ref "R64") (pin "1") (pinfunction "1_1") (pintype "passive"))
      (node (ref "R7") (pin "2") (pinfunction "2_2") (pintype "passive"))
      (node (ref "R77") (pin "2") (pinfunction "2_2") (pintype "passive"))
      (node (ref "R89") (pin "2") (pinfunction "2_2") (pintype "passive"))
      (node (ref "R90") (pin "1") (pinfunction "1_1") (pintype "passive"))
      (node (ref "U1") (pin "15") (pinfunction "~{RST}_15") (pintype "bidirectional"))
      (node (ref "U15") (pin "6") (pinfunction "V_6") (pintype "bidirectional"))
      (node (ref "U3") (pin "P$4") (pinfunction "VCC_P$4") (pintype "bidirectional"))
      (node (ref "U_DAISY") (pin "38") (pinfunction "+3V3_D_38") (pintype "bidirectional"))
      (node (ref "U_DAISY") (pin "B38") (pinfunction "+3V3_D_B38") (pintype "bidirectional"))
    )
    (net (code "3") (name "+3V3_OLED") (class "Default")
      (node (ref "C62") (pin "1") (pinfunction "1_1") (pintype "passive"))
      (node (ref "L3") (pin "2") (pinfunction "P$1_2") (pintype "bidirectional"))
      (node (ref "R95") (pin "2") (pinfunction "2_2") (pintype "passive"))
      (node (ref "U_OLED") (pin "2") (pinfunction "VCC_2") (pintype "bidirectional"))
    )
    (net (code "4") (name "+5V") (class "Default")
      (node (ref "C1") (pin "1") (pinfunction "1_1") (pintype "passive"))
      (node (ref "C4") (pin "1") (pinfunction "1_1") (pintype "passive"))
      (node (ref "C57") (pin "1") (pinfunction "1_1") (pintype "passive"))
      (node (ref "FB8") (pin "2") (pinfunction "2_2") (pintype "passive"))
      (node (ref "U1") (pin "24") (pinfunction "VCC_24") (pintype "bidirectional"))
    )
    (net (code "5") (name "+5V_ISOL") (class "Default")
      (node (ref "C42") (pin "+") (pinfunction "POS_+") (pintype "passive"))
      (node (ref "C43") (pin "2") (pinfunction "2_2") (pintype "passive"))
      (node (ref "FB1") (pin "2") (pinfunction "2_2") (pintype "passive"))
      (node (ref "U_DAISY") (pin "39") (pinfunction "V_IN_39") (pintype "bidirectional"))
      (node (ref "U_DAISY") (pin "B39") (pinfunction "V_IN_B39") (pintype "bidirectional"))
    )
    (net (code "6") (name "+12V") (class "Default")
      (node (ref "C20") (pin "1") (pinfunction "1_1") (pintype "passive"))
      (node (ref "C22") (pin "1") (pinfunction "1_1") (pintype "passive"))
      (node (ref "C29") (pin "1") (pinfunction "1_1") (pintype "passive"))
      (node (ref "C33") (pin "1") (pinfunction "1_1") (pintype "passive"))
      (node (ref "C34") (pin "1") (pinfunction "1_1") (pintype "passive"))
      (node (ref "C36") (pin "1") (pinfunction "1_1") (pintype "passive"))
      (node (ref "C44") (pin "1") (pinfunction "1_1") (pintype "passive"))
      (node (ref "C50") (pin "1") (pinfunction "1_1") (pintype "passive"))
      (node (ref "C58") (pin "1") (pinfunction "1_1") (pintype "passive"))
      (node (ref "C9") (pin "1") (pinfunction "1_1") (pintype "passive"))
      (node (ref "D1") (pin "C") (pinfunction "C_C") (pintype "passive"))
      (node (ref "FB5") (pin "1") (pinfunction "1_1") (pintype "passive"))
      (node (ref "R62") (pin "1") (pinfunction "1_1") (pintype "passive"))
      (node (ref "R65") (pin "1") (pinfunction "1_1") (pintype "passive"))
      (node (ref "U11") (pin "4") (pinfunction "V+_4") (pintype "power_in"))
      (node (ref "U13") (pin "4") (pinfunction "V+_4") (pintype "power_in"))
      (node (ref "U14") (pin "4") (pinfunction "V+_4") (pintype "power_in"))
      (node (ref "U16") (pin "4") (pinfunction "V+_4") (pintype "power_in"))
      (node (ref "U2") (pin "3") (pinfunction "IN_3") (pintype "input"))
      (node (ref "U4") (pin "4") (pinfunction "V+_4") (pintype "power_in"))
      (node (ref "U5") (pin "4") (pinfunction "V+_4") (pintype "power_in"))
    )
    (net (code "7") (name "-10V_REF") (class "Default")
      (node (ref "C13") (pin "1") (pinfunction "1_1") (pintype "passive"))
      (node (ref "R106") (pin "1") (pinfunction "1_1") (pintype "passive"))
      (node (ref "R18") (pin "1") (pinfunction "1_1") (pintype "passive"))
      (node (ref "R23") (pin "1") (pinfunction "1_1") (pintype "passive"))
      (node (ref "R26") (pin "1") (pinfunction "1_1") (pintype "passive"))
      (node (ref "R31") (pin "1") (pinfunction "1_1") (pintype "passive"))
      (node (ref "U6") (pin "2") (pinfunction "A_2") (pintype "passive"))
    )
    (net (code "8") (name "-12V") (class "Default")
      (node (ref "C10") (pin "2") (pinfunction "2_2") (pintype "passive"))
      (node (ref "C21") (pin "2") (pinfunction "2_2") (pintype "passive"))
      (node (ref "C23") (pin "2") (pinfunction "2_2") (pintype "passive"))
      (node (ref "C30") (pin "2") (pinfunction "2_2") (pintype "passive"))
      (node (ref "C35") (pin "2") (pinfunction "2_2") (pintype "passive"))
      (node (ref "C37") (pin "2") (pinfunction "2_2") (pintype "passive"))
      (node (ref "C45") (pin "2") (pinfunction "2_2") (pintype "passive"))
      (node (ref "C51") (pin "2") (pinfunction "2_2") (pintype "passive"))
      (node (ref "D2") (pin "A") (pinfunction "A_A") (pintype "passive"))
      (node (ref "R18") (pin "2") (pinfunction "2_2") (pintype "passive"))
      (node (ref "R68") (pin "1") (pinfunction "1_1") (pintype "passive"))
      (node (ref "R69") (pin "1") (pinfunction "1_1") (pintype "passive"))
      (node (ref "U11") (pin "11") (pinfunction "V-_11") (pintype "power_in"))
      (node (ref "U13") (pin "11") (pinfunction "V-_11") (pintype "power_in"))
      (node (ref "U14") (pin "11") (pinfunction "V-_11") (pintype "power_in"))
      (node (ref "U16") (pin "11") (pinfunction "V-_11") (pintype "power_in"))
      (node (ref "U4") (pin "11") (pinfunction "V-_11") (pintype "power_in"))
      (node (ref "U5") (pin "11") (pinfunction "V-_11") (pintype "power_in"))
    )
    (net (code "9") (name "ADC_CTRL_1") (class "Default")
      (node (ref "C54") (pin "2") (pinfunction "2_2") (pintype "passive"))
      (node (ref "R105") (pin "2") (pinfunction "2_2") (pintype "passive"))
      (node (ref "U7") (pin "8") (pinfunction "OUT_8") (pintype "output"))
      (node (ref "U_DAISY") (pin "22") (pinfunction "GPIO15(ADC0)_22") (pintype "bidirectional"))
      (node (ref "U_DAISY") (pin "B22") (pinfunction "GPIO15(ADC0)_B22") (pintype "bidirectional"))
    )
    (net (code "10") (name "ADC_CTRL_2") (class "Default")
      (node (ref "C11") (pin "2") (pinfunction "2_2") (pintype "passive"))
      (node (ref "R22") (pin "2") (pinfunction "2_2") (pintype "passive"))
      (node (ref "U7") (pin "7") (pinfunction "OUT_7") (pintype "output"))
      (node (ref "U_DAISY") (pin "23") (pinfunction "GPIO16(ADC1)_23") (pintype "bidirectional"))
      (node (ref "U_DAISY") (pin "B23") (pinfunction "GPIO16(ADC1)_B23") (pintype "bidirectional"))
    )
    (net (code "11") (name "ADC_CTRL_3") (class "Default")
      (node (ref "C12") (pin "2") (pinfunction "2_2") (pintype "passive"))
      (node (ref "R25") (pin "2") (pinfunction "2_2") (pintype "passive"))
      (node (ref "U7") (pin "1") (pinfunction "OUT_1") (pintype "output"))
      (node (ref "U_DAISY") (pin "28") (pinfunction "GPIO21(ADC6)_28") (pintype "bidirectional"))
      (node (ref "U_DAISY") (pin "B28") (pinfunction "GPIO21(ADC6)_B28") (pintype "bidirectional"))
    )
    (net (code "12") (name "ADC_CTRL_4") (class "Default")
      (node (ref "C15") (pin "2") (pinfunction "2_2") (pintype "passive"))
      (node (ref "R33") (pin "2") (pinfunction "2_2") (pintype "passive"))
      (node (ref "U7") (pin "14") (pinfunction "OUT_14") (pintype "output"))
      (node (ref "U_DAISY") (pin "25") (pinfunction "GPIO18(ADC3)_25") (pintype "bidirectional"))
      (node (ref "U_DAISY") (pin "B25") (pinfunction "GPIO18(ADC3)_B25") (pintype "bidirectional"))
    )
    (net (code "13") (name "AK4556_RST") (class "Default")
      (node (ref "R92") (pin "2") (pinfunction "2_2") (pintype "passive"))
      (node (ref "R93") (pin "2") (pinfunction "2_2") (pintype "passive"))
      (node (ref "U_DAISY") (pin "36") (pinfunction "GPIO29(USB_HS_D_-)_36") (pintype "bidirectional"))
      (node (ref "U_DAISY") (pin "B36") (pinfunction "GPIO29(USB_HS_D_-)_B36") (pintype "bidirectional"))
    )
    (net (code "14") (name "AUDIO_IN_1") (class "Default")
      (node (ref "J_AUDIO_IN_1") (pin "3") (pinfunction "TIP_3") (pintype "passive"))
      (node (ref "R55") (pin "1") (pinfunction "1_1") (pintype "passive"))
      (node (ref "R70") (pin "2") (pinfunction "2_2") (pintype "passive"))
    )
    (net (code "15") (name "AUDIO_IN_2") (class "Default")
      (node (ref "J_AUDIO_IN_2") (pin "3") (pinfunction "TIP_3") (pintype "passive"))
      (node (ref "R60") (pin "1") (pinfunction "1_1") (pintype "passive"))
      (node (ref "R75") (pin "2") (pinfunction "2_2") (pintype "passive"))
    )
    (net (code "16") (name "AUDIO_IN_3") (class "Default")
      (node (ref "J_AUDIO_IN_3") (pin "3") (pinfunction "TIP_3") (pintype "passive"))
      (node (ref "R20") (pin "1") (pinfunction "1_1") (pintype "passive"))
      (node (ref "R76") (pin "2") (pinfunction "2_2") (pintype "passive"))
    )
    (net (code "17") (name "AUDIO_IN_4") (class "Default")
      (node (ref "J_AUDIO_IN_4") (pin "3") (pinfunction "TIP_3") (pintype "passive"))
      (node (ref "R40") (pin "1") (pinfunction "1_1") (pintype "passive"))
    )
    (net (code "18") (name "AUDIO_OUT_1") (class "Default")
      (node (ref "J_AUDIO_OUT_1") (pin "3") (pinfunction "TIP_3") (pintype "passive"))
      (node (ref "R67") (pin "2") (pinfunction "2_2") (pintype "passive"))
    )
    (net (code "19") (name "AUDIO_OUT_2") (class "Default")
      (node (ref "J_AUDIO_OUT_2") (pin "3") (pinfunction "TIP_3") (pintype "passive"))
      (node (ref "R72") (pin "2") (pinfunction "2_2") (pintype "passive"))
    )
    (net (code "20") (name "AUDIO_OUT_3") (class "Default")
      (node (ref "J_AUDIO_OUT_3") (pin "3") (pinfunction "TIP_3") (pintype "passive"))
      (node (ref "R49") (pin "2") (pinfunction "2_2") (pintype "passive"))
    )
    (net (code "21") (name "AUDIO_OUT_4") (class "Default")
      (node (ref "J_AUDIO_OUT_4") (pin "3") (pinfunction "TIP_3") (pintype "passive"))
      (node (ref "R51") (pin "2") (pinfunction "2_2") (pintype "passive"))
    )
    (net (code "22") (name "CODEC_VCOM") (class "Default")
      (node (ref "C5") (pin "1") (pinfunction "1_1") (pintype "passive"))
      (node (ref "C59") (pin "1") (pinfunction "1_1") (pintype "passive"))
      (node (ref "C60") (pin "1") (pinfunction "1_1") (pintype "passive"))
      (node (ref "C8") (pin "1") (pinfunction "1_1") (pintype "passive"))
      (node (ref "U1") (pin "21") (pinfunction "VCOM_21") (pintype "bidirectional"))
      (node (ref "U14") (pin "10") (pinfunction "+IN_10") (pintype "input"))
      (node (ref "U14") (pin "12") (pinfunction "+IN_12") (pintype "input"))
    )
    (net (code "23") (name "CV_IN_1") (class "Default")
      (node (ref "J_CV_1") (pin "3") (pinfunction "TIP_3") (pintype "passive"))
      (node (ref "R107") (pin "1") (pinfunction "1_1") (pintype "passive"))
    )
    (net (code "24") (name "CV_IN_2") (class "Default")
      (node (ref "J_CV_2") (pin "3") (pinfunction "TIP_3") (pintype "passive"))
      (node (ref "R24") (pin "1") (pinfunction "1_1") (pintype "passive"))
    )
    (net (code "25") (name "CV_IN_3") (class "Default")
      (node (ref "J_CV_3") (pin "3") (pinfunction "TIP_3") (pintype "passive"))
      (node (ref "R27") (pin "1") (pinfunction "1_1") (pintype "passive"))
    )
    (net (code "26") (name "CV_IN_4") (class "Default")
      (node (ref "J_CV_4") (pin "3") (pinfunction "TIP_3") (pintype "passive"))
      (node (ref "R32") (pin "1") (pinfunction "1_1") (pintype "passive"))
    )
    (net (code "27") (name "DAC1_OUT1") (class "Default")
      (node (ref "R8") (pin "2") (pinfunction "2_2") (pintype "passive"))
      (node (ref "U_DAISY") (pin "30") (pinfunction "GPIO23(ADC8/DAC1)_30") (pintype "bidirectional"))
      (node (ref "U_DAISY") (pin "B30") (pinfunction "GPIO23(ADC8/DAC1)_B30") (pintype "bidirectional"))
    )
    (net (code "28") (name "DAC1_OUT1_") (class "Default")
      (node (ref "J_CV_OUT_1") (pin "3") (pinfunction "TIP_3") (pintype "passive"))
      (node (ref "R12") (pin "1") (pinfunction "1_1") (pintype "passive"))
    )
    (net (code "29") (name "DAC1_OUT2") (class "Default")
      (node (ref "R10") (pin "2") (pinfunction "2_2") (pintype "passive"))
      (node (ref "U_DAISY") (pin "29") (pinfunction "GPIO22(ADC7/DAC2)_29") (pintype "bidirectional"))
      (node (ref "U_DAISY") (pin "B29") (pinfunction "GPIO22(ADC7/DAC2)_B29") (pintype "bidirectional"))
    )
    (net (code "30") (name "DAC1_OUT2_") (class "Default")
      (node (ref "J_CV_OUT_2") (pin "3") (pinfunction "TIP_3") (pintype "passive"))
      (node (ref "R13") (pin "1") (pinfunction "1_1") (pintype "passive"))
    )
    (net (code "31") (name "ENC_A") (class "Default")
      (node (ref "ENC_1") (pin "A") (pinfunction "A_A") (pintype "passive"))
      (node (ref "U_DAISY") (pin "13") (pinfunction "GPIO12(I2C1_SDA)_13") (pintype "bidirectional"))
      (node (ref "U_DAISY") (pin "B13") (pinfunction "GPIO12(I2C1_SDA)_B13") (pintype "bidirectional"))
    )
    (net (code "32") (name "ENC_B") (class "Default")
      (node (ref "ENC_1") (pin "B") (pinfunction "B_B") (pintype "passive"))
      (node (ref "U_DAISY") (pin "12") (pinfunction "GPIO11(I2C1_SCL)_12") (pintype "bidirectional"))
      (node (ref "U_DAISY") (pin "B12") (pinfunction "GPIO11(I2C1_SCL)_B12") (pintype "bidirectional"))
    )
    (net (code "33") (name "ENC_CLICK") (class "Default")
      (node (ref "ENC_1") (pin "E") (pinfunction "2_E") (pintype "passive"))
      (node (ref "U_DAISY") (pin "1") (pinfunction "GPIO0(USB_HS_ID)_1") (pintype "bidirectional"))
      (node (ref "U_DAISY") (pin "B1") (pinfunction "GPIO0(USB_HS_ID)_B1") (pintype "bidirectional"))
    )
    (net (code "34") (name "EXT_AUDIO_IN_L") (class "Default")
      (node (ref "R46") (pin "2") (pinfunction "2_2") (pintype "passive"))
      (node (ref "U1") (pin "25") (pinfunction "VINL_25") (pintype "bidirectional"))
    )
    (net (code "35") (name "EXT_AUDIO_IN_R") (class "Default")
      (node (ref "R47") (pin "2") (pinfunction "2_2") (pintype "passive"))
      (node (ref "U1") (pin "26") (pinfunction "VINR_26") (pintype "bidirectional"))
    )
    (net (code "36") (name "EXT_AUDIO_OUT_L") (class "Default")
      (node (ref "C55") (pin "1") (pinfunction "1_1") (pintype "passive"))
      (node (ref "U1") (pin "20") (pinfunction "VOUTL+_20") (pintype "bidirectional"))
    )
    (net (code "37") (name "EXT_AUDIO_OUT_R") (class "Default")
      (node (ref "C56") (pin "1") (pinfunction "1_1") (pintype "passive"))
      (node (ref "U1") (pin "18") (pinfunction "VOUTR+_18") (pintype "bidirectional"))
    )
    (net (code "38") (name "GATE_IN_1") (class "Default")
      (node (ref "R30") (pin "1") (pinfunction "1_1") (pintype "passive"))
      (node (ref "U_DAISY") (pin "27") (pinfunction "GPIO20(ADC5)_27") (pintype "bidirectional"))
      (node (ref "U_DAISY") (pin "B27") (pinfunction "GPIO20(ADC5)_B27") (pintype "bidirectional"))
    )
    (net (code "39") (name "GATE_IN_2") (class "Default")
      (node (ref "R37") (pin "1") (pinfunction "1_1") (pintype "passive"))
      (node (ref "U_DAISY") (pin "26") (pinfunction "GPIO19(ADC4)_26") (pintype "bidirectional"))
      (node (ref "U_DAISY") (pin "B26") (pinfunction "GPIO19(ADC4)_B26") (pintype "bidirectional"))
    )
    (net (code "40") (name "GATE_OUT") (class "Default")
      (node (ref "R112") (pin "2") (pinfunction "2_2") (pintype "passive"))
      (node (ref "U_DAISY") (pin "24") (pinfunction "GPIO17(ADC2)_24") (pintype "bidirectional"))
      (node (ref "U_DAISY") (pin "B24") (pinfunction "GPIO17(ADC2)_B24") (pintype "bidirectional"))
    )
    (net (code "41") (name "GND") (class "Default")
      (node (ref "C1") (pin "2") (pinfunction "2_2") (pintype "passive"))
      (node (ref "C10") (pin "1") (pinfunction "1_1") (pintype "passive"))
      (node (ref "C13") (pin "2") (pinfunction "2_2") (pintype "passive"))
      (node (ref "C14") (pin "2") (pinfunction "2_2") (pintype "passive"))
      (node (ref "C16") (pin "2") (pinfunction "2_2") (pintype "passive"))
      (node (ref "C2") (pin "2") (pinfunction "2_2") (pintype "passive"))
      (node (ref "C20") (pin "2") (pinfunction "2_2") (pintype "passive"))
      (node (ref "C21") (pin "1") (pinfunction "1_1") (pintype "passive"))
      (node (ref "C22") (pin "2") (pinfunction "2_2") (pintype "passive"))
      (node (ref "C23") (pin "1") (pinfunction "1_1") (pintype "passive"))
      (node (ref "C29") (pin "2") (pinfunction "2_2") (pintype "passive"))
      (node (ref "C3") (pin "2") (pinfunction "2_2") (pintype "passive"))
      (node (ref "C30") (pin "1") (pinfunction "1_1") (pintype "passive"))
      (node (ref "C31") (pin "2") (pinfunction "2_2") (pintype "passive"))
      (node (ref "C33") (pin "2") (pinfunction "2_2") (pintype "passive"))
      (node (ref "C34") (pin "2") (pinfunction "2_2") (pintype "passive"))
      (node (ref "C35") (pin "1") (pinfunction "1_1") (pintype "passive"))
      (node (ref "C36") (pin "2") (pinfunction "2_2") (pintype "passive"))
      (node (ref "C37") (pin "1") (pinfunction "1_1") (pintype "passive"))
      (node (ref "C39") (pin "1") (pinfunction "1_1") (pintype "passive"))
      (node (ref "C4") (pin "2") (pinfunction "2_2") (pintype "passive"))
      (node (ref "C42") (pin "-") (pinfunction "NEG_-") (pintype "passive"))
      (node (ref "C43") (pin "1") (pinfunction "1_1") (pintype "passive"))
      (node (ref "C44") (pin "2") (pinfunction "2_2") (pintype "passive"))
      (node (ref "C45") (pin "1") (pinfunction "1_1") (pintype "passive"))
      (node (ref "C5") (pin "2") (pinfunction "2_2") (pintype "passive"))
      (node (ref "C50") (pin "2") (pinfunction "2_2") (pintype "passive"))
      (node (ref "C51") (pin "1") (pinfunction "1_1") (pintype "passive"))
      (node (ref "C57") (pin "2") (pinfunction "2_2") (pintype "passive"))
      (node (ref "C58") (pin "2") (pinfunction "2_2") (pintype "passive"))
      (node (ref "C59") (pin "2") (pinfunction "2_2") (pintype "passive"))
      (node (ref "C60") (pin "2") (pinfunction "2_2") (pintype "passive"))
      (node (ref "C61") (pin "2") (pinfunction "2_2") (pintype "passive"))
      (node (ref "C62") (pin "2") (pinfunction "2_2") (pintype "passive"))
      (node (ref "C8") (pin "2") (pinfunction "2_2") (pintype "passive"))
      (node (ref "C9") (pin "2") (pinfunction "2_2") (pintype "passive"))
      (node (ref "D4") (pin "A") (pinfunction "A_A") (pintype "passive"))
      (node (ref "ENC_1") (pin "C") (pinfunction "C_C") (pintype "passive"))
      (node (ref "ENC_1") (pin "D") (pinfunction "1_D") (pintype "passive"))
      (node (ref "EP1") (pin "10") (pinfunction "GND_10") (pintype "bidirectional"))
      (node (ref "EP1") (pin "11") (pinfunction "GND_11") (pintype "bidirectional"))
      (node (ref "EP1") (pin "12") (pinfunction "GND_12") (pintype "bidirectional"))
      (node (ref "EP1") (pin "13") (pinfunction "GND_13") (pintype "bidirectional"))
      (node (ref "EP1") (pin "14") (pinfunction "GND_14") (pintype "bidirectional"))
      (node (ref "EP1") (pin "9") (pinfunction "GND_9") (pintype "bidirectional"))
      (node (ref "J_AUDIO_IN_1") (pin "1") (pinfunction "GND_1") (pintype "passive"))
      (node (ref "J_AUDIO_IN_2") (pin "1") (pinfunction "GND_1") (pintype "passive"))
      (node (ref "J_AUDIO_IN_3") (pin "1") (pinfunction "GND_1") (pintype "passive"))
      (node (ref "J_AUDIO_IN_4") (pin "1") (pinfunction "GND_1") (pintype "passive"))
      (node (ref "J_AUDIO_OUT_1") (pin "1") (pinfunction "GND_1") (pintype "passive"))
      (node (ref "J_AUDIO_OUT_2") (pin "1") (pinfunction "GND_1") (pintype "passive"))
      (node (ref "J_AUDIO_OUT_3") (pin "1") (pinfunction "GND_1") (pintype "passive"))
      (node (ref "J_AUDIO_OUT_4") (pin "1") (pinfunction "GND_1") (pintype "passive"))
      (node (ref "J_CV_1") (pin "1") (pinfunction "GND_1") (pintype "passive"))
      (node (ref "J_CV_2") (pin "1") (pinfunction "GND_1") (pintype "passive"))
      (node (ref "J_CV_3") (pin "1") (pinfunction "GND_1") (pintype "passive"))
      (node (ref "J_CV_4") (pin "1") (pinfunction "GND_1") (pintype "passive"))
      (node (ref "J_CV_OUT_1") (pin "1") (pinfunction "GND_1") (pintype "passive"))
      (node (ref "J_CV_OUT_2") (pin "1") (pinfunction "GND_1") (pintype "passive"))
      (node (ref "J_GATE_IN_1") (pin "1") (pinfunction "GND_1") (pintype "passive"))
      (node (ref "J_GATE_IN_2") (pin "1") (pinfunction "GND_1") (pintype "passive"))
      (node (ref "J_GATE_OUT") (pin "1") (pinfunction "GND_1") (pintype "passive"))
      (node (ref "J_MIDI_IN") (pin "GND") (pinfunction "GND_GND") (pintype "passive"))
      (node (ref "J_MIDI_OUT") (pin "GND") (pinfunction "GND_GND") (pintype "passive"))
      (node (ref "Q1") (pin "E") (pinfunction "E_E") (pintype "passive"))
      (node (ref "Q2") (pin "E") (pinfunction "E_E") (pintype "passive"))
      (node (ref "R28") (pin "1") (pinfunction "1_1") (pintype "passive"))
      (node (ref "R35") (pin "1") (pinfunction "1_1") (pintype "passive"))
      (node (ref "R85") (pin "1") (pinfunction "1_1") (pintype "passive"))
      (node (ref "R86") (pin "1") (pinfunction "1_1") (pintype "passive"))
      (node (ref "R91") (pin "2") (pinfunction "2_2") (pintype "passive"))
      (node (ref "R94") (pin "2") (pinfunction "2_2") (pintype "passive"))
      (node (ref "U$1") (pin "P$4") (pinfunction "OUT-_P$4") (pintype "bidirectional"))
      (node (ref "U1") (pin "16") (pinfunction "SGND_16") (pintype "bidirectional"))
      (node (ref "U1") (pin "22") (pinfunction "AGND2_22") (pintype "bidirectional"))
      (node (ref "U1") (pin "23") (pinfunction "AGND1_23") (pintype "bidirectional"))
      (node (ref "U1") (pin "27") (pinfunction "MS/ADR/IFMD_27") (pintype "bidirectional"))
      (node (ref "U1") (pin "8") (pinfunction "DGND_8") (pintype "bidirectional"))
      (node (ref "U11") (pin "10") (pinfunction "+IN_10") (pintype "input"))
      (node (ref "U11") (pin "12") (pinfunction "+IN_12") (pintype "input"))
      (node (ref "U11") (pin "3") (pinfunction "+IN_3") (pintype "input"))
      (node (ref "U11") (pin "5") (pinfunction "+IN_5") (pintype "input"))
      (node (ref "U13") (pin "10") (pinfunction "+IN_10") (pintype "input"))
      (node (ref "U13") (pin "12") (pinfunction "+IN_12") (pintype "input"))
      (node (ref "U13") (pin "3") (pinfunction "+IN_3") (pintype "input"))
      (node (ref "U13") (pin "5") (pinfunction "+IN_5") (pintype "input"))
      (node (ref "U14") (pin "3") (pinfunction "+IN_3") (pintype "input"))
      (node (ref "U14") (pin "5") (pinfunction "+IN_5") (pintype "input"))
      (node (ref "U15") (pin "5") (pinfunction "GND_5") (pintype "bidirectional"))
      (node (ref "U16") (pin "10") (pinfunction "+IN_10") (pintype "input"))
      (node (ref "U16") (pin "12") (pinfunction "+IN_12") (pintype "input"))
      (node (ref "U16") (pin "3") (pinfunction "+IN_3") (pintype "input"))
      (node (ref "U16") (pin "5") (pinfunction "+IN_5") (pintype "input"))
      (node (ref "U2") (pin "1") (pinfunction "GND_1") (pintype "input"))
      (node (ref "U3") (pin "GND1") (pinfunction "SHIELD_GND1") (pintype "bidirectional"))
      (node (ref "U3") (pin "GND2") (pinfunction "SHIELD_GND2") (pintype "bidirectional"))
      (node (ref "U3") (pin "P$6") (pinfunction "GND_P$6") (pintype "bidirectional"))
      (node (ref "U4") (pin "10") (pinfunction "+IN_10") (pintype "input"))
      (node (ref "U4") (pin "12") (pinfunction "+IN_12") (pintype "input"))
      (node (ref "U4") (pin "3") (pinfunction "+IN_3") (pintype "input"))
      (node (ref "U4") (pin "5") (pinfunction "+IN_5") (pintype "input"))
      (node (ref "U5") (pin "10") (pinfunction "+IN_10") (pintype "input"))
      (node (ref "U5") (pin "12") (pinfunction "+IN_12") (pintype "input"))
      (node (ref "U5") (pin "3") (pinfunction "+IN_3") (pintype "input"))
      (node (ref "U5") (pin "5") (pinfunction "+IN_5") (pintype "input"))
      (node (ref "U6") (pin "1") (pinfunction "C_1") (pintype "passive"))
      (node (ref "U7") (pin "10") (pinfunction "+IN_10") (pintype "input"))
      (node (ref "U7") (pin "11") (pinfunction "V-_11") (pintype "power_in"))
      (node (ref "U7") (pin "12") (pinfunction "+IN_12") (pintype "input"))
      (node (ref "U7") (pin "3") (pinfunction "+IN_3") (pintype "input"))
      (node (ref "U7") (pin "5") (pinfunction "+IN_5") (pintype "input"))
      (node (ref "U9") (pin "2") (pinfunction "GND_2") (pintype "passive"))
      (node (ref "U9") (pin "7") (pinfunction "EPAD_7") (pintype "passive"))
      (node (ref "U_DAISY") (pin "20") (pinfunction "AGND_20") (pintype "bidirectional"))
      (node (ref "U_DAISY") (pin "40") (pinfunction "GND_40") (pintype "bidirectional"))
      (node (ref "U_DAISY") (pin "B20") (pinfunction "AGND_B20") (pintype "bidirectional"))
      (node (ref "U_DAISY") (pin "B40") (pinfunction "GND_B40") (pintype "bidirectional"))
      (node (ref "U_OLED") (pin "1") (pinfunction "GND_1") (pintype "bidirectional"))
      (node (ref "VR_1") (pin "1") (pinfunction "1_1") (pintype "passive"))
      (node (ref "VR_2") (pin "1") (pinfunction "1_1") (pintype "passive"))
      (node (ref "VR_3") (pin "1") (pinfunction "1_1") (pintype "passive"))
      (node (ref "VR_4") (pin "1") (pinfunction "1_1") (pintype "passive"))
    )
    (net (code "42") (name "I2C2_SCL") (class "Default")
      (node (ref "R77") (pin "1") (pinfunction "1_1") (pintype "passive"))
      (node (ref "R92") (pin "1") (pinfunction "1_1") (pintype "passive"))
      (node (ref "U1") (pin "1") (pinfunction "MC/SCL/FMT_1") (pintype "bidirectional"))
    )
    (net (code "43") (name "I2C2_SDA") (class "Default")
      (node (ref "R89") (pin "1") (pinfunction "1_1") (pintype "passive"))
      (node (ref "R91") (pin "1") (pinfunction "1_1") (pintype "passive"))
      (node (ref "R93") (pin "1") (pinfunction "1_1") (pintype "passive"))
      (node (ref "U1") (pin "2") (pinfunction "MD/SDA/DEMP_2") (pintype "bidirectional"))
    )
    (net (code "44") (name "INT_AUDIO_IN_L") (class "Default")
      (node (ref "R82") (pin "2") (pinfunction "2_2") (pintype "passive"))
      (node (ref "U_DAISY") (pin "16") (pinfunction "AUDIO_IN_L_16") (pintype "bidirectional"))
      (node (ref "U_DAISY") (pin "B16") (pinfunction "AUDIO_IN_L_B16") (pintype "bidirectional"))
    )
    (net (code "45") (name "INT_AUDIO_IN_R") (class "Default")
      (node (ref "R98") (pin "2") (pinfunction "2_2") (pintype "passive"))
      (node (ref "U_DAISY") (pin "17") (pinfunction "AUDIO_IN_R_17") (pintype "bidirectional"))
      (node (ref "U_DAISY") (pin "B17") (pinfunction "AUDIO_IN_R_B17") (pintype "bidirectional"))
    )
    (net (code "46") (name "INT_AUDIO_OUT_L") (class "Default")
      (node (ref "R102") (pin "1") (pinfunction "1_1") (pintype "passive"))
      (node (ref "U_DAISY") (pin "18") (pinfunction "AUDIO_OUT_L_18") (pintype "bidirectional"))
      (node (ref "U_DAISY") (pin "B18") (pinfunction "AUDIO_OUT_L_B18") (pintype "bidirectional"))
    )
    (net (code "47") (name "INT_AUDIO_OUT_R") (class "Default")
      (node (ref "R104") (pin "1") (pinfunction "1_1") (pintype "passive"))
      (node (ref "U_DAISY") (pin "19") (pinfunction "AUDIO_OUT_R_19") (pintype "bidirectional"))
      (node (ref "U_DAISY") (pin "B19") (pinfunction "AUDIO_OUT_R_B19") (pintype "bidirectional"))
    )
    (net (code "48") (name "KNOB_1") (class "Default")
      (node (ref "R108") (pin "1") (pinfunction "1_1") (pintype "passive"))
      (node (ref "VR_1") (pin "2") (pinfunction "2_2") (pintype "passive"))
    )
    (net (code "49") (name "KNOB_2") (class "Default")
      (node (ref "R109") (pin "1") (pinfunction "1_1") (pintype "passive"))
      (node (ref "VR_2") (pin "2") (pinfunction "2_2") (pintype "passive"))
    )
    (net (code "50") (name "KNOB_3") (class "Default")
      (node (ref "R110") (pin "1") (pinfunction "1_1") (pintype "passive"))
      (node (ref "VR_3") (pin "2") (pinfunction "2_2") (pintype "passive"))
    )
    (net (code "51") (name "KNOB_4") (class "Default")
      (node (ref "R111") (pin "1") (pinfunction "1_1") (pintype "passive"))
      (node (ref "VR_4") (pin "2") (pinfunction "2_2") (pintype "passive"))
    )
    (net (code "52") (name "MIDI_IN_A") (class "Default")
      (node (ref "R63") (pin "2") (pinfunction "2_2") (pintype "passive"))
      (node (ref "R78") (pin "1") (pinfunction "1_1") (pintype "passive"))
      (node (ref "R79") (pin "1") (pinfunction "1_1") (pintype "passive"))
    )
    (net (code "53") (name "MIDI_IN_B") (class "Default")
      (node (ref "D5") (pin "A") (pinfunction "A_A") (pintype "passive"))
      (node (ref "R83") (pin "1") (pinfunction "1_1") (pintype "passive"))
      (node (ref "R84") (pin "1") (pinfunction "1_1") (pintype "passive"))
      (node (ref "U15") (pin "2") (pinfunction "C_2") (pintype "bidirectional"))
    )
    (net (code "54") (name "MIDI_IN_RING") (class "Default")
      (node (ref "J_MIDI_IN") (pin "RING") (pinfunction "NORM_RING") (pintype "passive"))
      (node (ref "R79") (pin "2") (pinfunction "2_2") (pintype "passive"))
      (node (ref "R84") (pin "2") (pinfunction "2_2") (pintype "passive"))
    )
    (net (code "55") (name "MIDI_IN_TIP") (class "Default")
      (node (ref "J_MIDI_IN") (pin "TIP") (pinfunction "TIP_TIP") (pintype "passive"))
      (node (ref "R78") (pin "2") (pinfunction "2_2") (pintype "passive"))
      (node (ref "R83") (pin "2") (pinfunction "2_2") (pintype "passive"))
    )
    (net (code "56") (name "Net-(C38-NEG)") (class "Default")
      (node (ref "C32") (pin "1") (pinfunction "1_1") (pintype "passive"))
      (node (ref "C38") (pin "-") (pinfunction "NEG_-") (pintype "passive"))
      (node (ref "L2") (pin "P$1") (pinfunction "P$1_P$1") (pintype "bidirectional"))
      (node (ref "R68") (pin "2") (pinfunction "2_2") (pintype "passive"))
      (node (ref "R69") (pin "2") (pinfunction "2_2") (pintype "passive"))
    )
    (net (code "57") (name "Net-(C38-POS)") (class "Default")
      (node (ref "C32") (pin "2") (pinfunction "2_2") (pintype "passive"))
      (node (ref "C38") (pin "+") (pinfunction "POS_+") (pintype "passive"))
      (node (ref "L1") (pin "P$1") (pinfunction "P$1_P$1") (pintype "bidirectional"))
      (node (ref "R62") (pin "2") (pinfunction "2_2") (pintype "passive"))
      (node (ref "R65") (pin "2") (pinfunction "2_2") (pintype "passive"))
    )
    (net (code "58") (name "Net-(C40-Pad2)") (class "Default")
      (node (ref "C40") (pin "2") (pinfunction "2_2") (pintype "passive"))
      (node (ref "R42") (pin "1") (pinfunction "1_1") (pintype "passive"))
    )
    (net (code "59") (name "Net-(C41-Pad2)") (class "Default")
      (node (ref "C41") (pin "2") (pinfunction "2_2") (pintype "passive"))
      (node (ref "R44") (pin "1") (pinfunction "1_1") (pintype "passive"))
    )
    (net (code "60") (name "Net-(C55-Pad2)") (class "Default")
      (node (ref "C55") (pin "2") (pinfunction "2_2") (pintype "passive"))
      (node (ref "R57") (pin "2") (pinfunction "2_2") (pintype "passive"))
      (node (ref "R85") (pin "2") (pinfunction "2_2") (pintype "passive"))
      (node (ref "R96") (pin "2") (pinfunction "2_2") (pintype "passive"))
    )
    (net (code "61") (name "Net-(C56-Pad2)") (class "Default")
      (node (ref "C56") (pin "2") (pinfunction "2_2") (pintype "passive"))
      (node (ref "R59") (pin "2") (pinfunction "2_2") (pintype "passive"))
      (node (ref "R86") (pin "2") (pinfunction "2_2") (pintype "passive"))
      (node (ref "R97") (pin "2") (pinfunction "2_2") (pintype "passive"))
    )
    (net (code "62") (name "Net-(D1-PadA)") (class "Default")
      (node (ref "D1") (pin "A") (pinfunction "A_A") (pintype "passive"))
      (node (ref "FB2") (pin "2") (pinfunction "2_2") (pintype "passive"))
    )
    (net (code "63") (name "Net-(D2-PadC)") (class "Default")
      (node (ref "D2") (pin "C") (pinfunction "C_C") (pintype "passive"))
      (node (ref "FB3") (pin "2") (pinfunction "2_2") (pintype "passive"))
    )
    (net (code "64") (name "Net-(EP1-+12VIN-Pad7)") (class "Default")
      (node (ref "EP1") (pin "7") (pinfunction "+12VIN_7") (pintype "bidirectional"))
      (node (ref "EP1") (pin "8") (pinfunction "+12VIN_8") (pintype "bidirectional"))
      (node (ref "FB2") (pin "1") (pinfunction "1_1") (pintype "passive"))
    )
    (net (code "65") (name "Net-(EP1--12VIN-Pad15)") (class "Default")
      (node (ref "EP1") (pin "15") (pinfunction "-12VIN_15") (pintype "bidirectional"))
      (node (ref "EP1") (pin "16") (pinfunction "-12VIN_16") (pintype "bidirectional"))
      (node (ref "FB3") (pin "1") (pinfunction "1_1") (pintype "passive"))
    )
    (net (code "66") (name "Net-(J_AUDIO_IN_2-NORM)") (class "Default")
      (node (ref "J_AUDIO_IN_2") (pin "2") (pinfunction "NORM_2") (pintype "passive"))
      (node (ref "R70") (pin "1") (pinfunction "1_1") (pintype "passive"))
    )
    (net (code "67") (name "Net-(J_AUDIO_IN_3-NORM)") (class "Default")
      (node (ref "J_AUDIO_IN_3") (pin "2") (pinfunction "NORM_2") (pintype "passive"))
      (node (ref "R75") (pin "1") (pinfunction "1_1") (pintype "passive"))
    )
    (net (code "68") (name "Net-(J_AUDIO_IN_4-NORM)") (class "Default")
      (node (ref "J_AUDIO_IN_4") (pin "2") (pinfunction "NORM_2") (pintype "passive"))
      (node (ref "R76") (pin "1") (pinfunction "1_1") (pintype "passive"))
    )
    (net (code "69") (name "Net-(J_GATE_IN_2-TIP)") (class "Default")
      (node (ref "J_GATE_IN_2") (pin "3") (pinfunction "TIP_3") (pintype "passive"))
      (node (ref "R34") (pin "1") (pinfunction "1_1") (pintype "passive"))
    )
    (net (code "70") (name "Net-(J_MIDI_OUT-NORM)") (class "Default")
      (node (ref "J_MIDI_OUT") (pin "RING") (pinfunction "NORM_RING") (pintype "passive"))
      (node (ref "R1") (pin "2") (pinfunction "2_2") (pintype "passive"))
    )
    (net (code "71") (name "Net-(J_MIDI_OUT-PadTIP)") (class "Default")
      (node (ref "J_MIDI_OUT") (pin "TIP") (pinfunction "TIP_TIP") (pintype "passive"))
      (node (ref "R2") (pin "1") (pinfunction "1_1") (pintype "passive"))
    )
    (net (code "72") (name "Net-(L3-P$2)") (class "Default")
      (node (ref "D4") (pin "C") (pinfunction "C_C") (pintype "passive"))
      (node (ref "L3") (pin "1") (pinfunction "P$2_1") (pintype "bidirectional"))
      (node (ref "U9") (pin "3") (pinfunction "SW_3") (pintype "passive"))
    )
    (net (code "73") (name "Net-(Q1-PadB)") (class "Default")
      (node (ref "Q1") (pin "B") (pinfunction "B_B") (pintype "passive"))
      (node (ref "R21") (pin "2") (pinfunction "2_2") (pintype "passive"))
      (node (ref "R28") (pin "2") (pinfunction "2_2") (pintype "passive"))
    )
    (net (code "74") (name "Net-(Q1-PadC)") (class "Default")
      (node (ref "Q1") (pin "C") (pinfunction "C_C") (pintype "passive"))
      (node (ref "R29") (pin "1") (pinfunction "1_1") (pintype "passive"))
      (node (ref "R30") (pin "2") (pinfunction "2_2") (pintype "passive"))
    )
    (net (code "75") (name "Net-(Q2-PadB)") (class "Default")
      (node (ref "Q2") (pin "B") (pinfunction "B_B") (pintype "passive"))
      (node (ref "R34") (pin "2") (pinfunction "2_2") (pintype "passive"))
      (node (ref "R35") (pin "2") (pinfunction "2_2") (pintype "passive"))
    )
    (net (code "76") (name "Net-(Q2-PadC)") (class "Default")
      (node (ref "Q2") (pin "C") (pinfunction "C_C") (pintype "passive"))
      (node (ref "R36") (pin "1") (pinfunction "1_1") (pintype "passive"))
      (node (ref "R37") (pin "2") (pinfunction "2_2") (pintype "passive"))
    )
    (net (code "77") (name "Net-(R43-Pad2)") (class "Default")
      (node (ref "R43") (pin "2") (pinfunction "2_2") (pintype "passive"))
      (node (ref "R87") (pin "2") (pinfunction "2_2") (pintype "passive"))
    )
    (net (code "78") (name "Net-(R45-Pad2)") (class "Default")
      (node (ref "R45") (pin "2") (pinfunction "2_2") (pintype "passive"))
      (node (ref "R88") (pin "2") (pinfunction "2_2") (pintype "passive"))
    )
    (net (code "79") (name "Net-(U$1-IN+)") (class "Default")
      (node (ref "L1") (pin "P$2") (pinfunction "P$2_P$2") (pintype "bidirectional"))
      (node (ref "U$1") (pin "P$2") (pinfunction "IN+_P$2") (pintype "bidirectional"))
    )
    (net (code "80") (name "Net-(U$1-IN-)") (class "Default")
      (node (ref "L2") (pin "P$2") (pinfunction "P$2_P$2") (pintype "bidirectional"))
      (node (ref "U$1") (pin "P$1") (pinfunction "IN-_P$1") (pintype "bidirectional"))
    )
    (net (code "81") (name "Net-(U$1-OUT+)") (class "Default")
      (node (ref "C39") (pin "2") (pinfunction "2_2") (pintype "passive"))
      (node (ref "FB1") (pin "1") (pinfunction "1_1") (pintype "passive"))
      (node (ref "U$1") (pin "P$5") (pinfunction "OUT+_P$5") (pintype "bidirectional"))
    )
    (net (code "82") (name "Net-(U1-MODE)") (class "Default")
      (node (ref "R90") (pin "2") (pinfunction "2_2") (pintype "passive"))
      (node (ref "U1") (pin "28") (pinfunction "MODE_28") (pintype "bidirectional"))
    )
    (net (code "83") (name "Net-(U2-OUT)") (class "Default")
      (node (ref "C31") (pin "1") (pinfunction "1_1") (pintype "passive"))
      (node (ref "FB8") (pin "1") (pinfunction "1_1") (pintype "passive"))
      (node (ref "U2") (pin "2") (pinfunction "OUT_2") (pintype "passive"))
      (node (ref "U2") (pin "TAB") (pinfunction "OUT1_TAB") (pintype "passive"))
    )
    (net (code "84") (name "Net-(U4A--IN)") (class "Default")
      (node (ref "C46") (pin "1") (pinfunction "1_1") (pintype "passive"))
      (node (ref "R55") (pin "2") (pinfunction "2_2") (pintype "passive"))
      (node (ref "R56") (pin "1") (pinfunction "1_1") (pintype "passive"))
      (node (ref "U4") (pin "2") (pinfunction "-IN_2") (pintype "input"))
    )
    (net (code "85") (name "Net-(U4A-OUT)") (class "Default")
      (node (ref "C46") (pin "2") (pinfunction "2_2") (pintype "passive"))
      (node (ref "R56") (pin "2") (pinfunction "2_2") (pintype "passive"))
      (node (ref "R73") (pin "1") (pinfunction "1_1") (pintype "passive"))
      (node (ref "U4") (pin "1") (pinfunction "OUT_1") (pintype "output"))
    )
    (net (code "86") (name "Net-(U4B--IN)") (class "Default")
      (node (ref "C47") (pin "1") (pinfunction "1_1") (pintype "passive"))
      (node (ref "R60") (pin "2") (pinfunction "2_2") (pintype "passive"))
      (node (ref "R61") (pin "1") (pinfunction "1_1") (pintype "passive"))
      (node (ref "U4") (pin "6") (pinfunction "-IN_6") (pintype "input"))
    )
    (net (code "87") (name "Net-(U4B-OUT)") (class "Default")
      (node (ref "C47") (pin "2") (pinfunction "2_2") (pintype "passive"))
      (node (ref "R61") (pin "2") (pinfunction "2_2") (pintype "passive"))
      (node (ref "R80") (pin "1") (pinfunction "1_1") (pintype "passive"))
      (node (ref "U4") (pin "7") (pinfunction "OUT_7") (pintype "output"))
    )
    (net (code "88") (name "Net-(U4C--IN)") (class "Default")
      (node (ref "C49") (pin "1") (pinfunction "1_1") (pintype "passive"))
      (node (ref "R80") (pin "2") (pinfunction "2_2") (pintype "passive"))
      (node (ref "R81") (pin "1") (pinfunction "1_1") (pintype "passive"))
      (node (ref "U4") (pin "9") (pinfunction "-IN_9") (pintype "input"))
    )
    (net (code "89") (name "Net-(U4C-OUT)") (class "Default")
      (node (ref "C49") (pin "2") (pinfunction "2_2") (pintype "passive"))
      (node (ref "R81") (pin "2") (pinfunction "2_2") (pintype "passive"))
      (node (ref "R98") (pin "1") (pinfunction "1_1") (pintype "passive"))
      (node (ref "U4") (pin "8") (pinfunction "OUT_8") (pintype "output"))
    )
    (net (code "90") (name "Net-(U4D--IN)") (class "Default")
      (node (ref "C48") (pin "1") (pinfunction "1_1") (pintype "passive"))
      (node (ref "R73") (pin "2") (pinfunction "2_2") (pintype "passive"))
      (node (ref "R74") (pin "1") (pinfunction "1_1") (pintype "passive"))
      (node (ref "U4") (pin "13") (pinfunction "-IN_13") (pintype "input"))
    )
    (net (code "91") (name "Net-(U4D-OUT)") (class "Default")
      (node (ref "C48") (pin "2") (pinfunction "2_2") (pintype "passive"))
      (node (ref "R74") (pin "2") (pinfunction "2_2") (pintype "passive"))
      (node (ref "R82") (pin "1") (pinfunction "1_1") (pintype "passive"))
      (node (ref "U4") (pin "14") (pinfunction "OUT_14") (pintype "output"))
    )
    (net (code "92") (name "Net-(U5A--IN)") (class "Default")
      (node (ref "R10") (pin "1") (pinfunction "1_1") (pintype "passive"))
      (node (ref "R11") (pin "2") (pinfunction "2_2") (pintype "passive"))
      (node (ref "U5") (pin "2") (pinfunction "-IN_2") (pintype "input"))
    )
    (net (code "93") (name "Net-(U5A-OUT)") (class "Default")
      (node (ref "R11") (pin "1") (pinfunction "1_1") (pintype "passive"))
      (node (ref "R16") (pin "2") (pinfunction "2_2") (pintype "passive"))
      (node (ref "U5") (pin "1") (pinfunction "OUT_1") (pintype "output"))
    )
    (net (code "94") (name "Net-(U5B--IN)") (class "Default")
      (node (ref "R8") (pin "1") (pinfunction "1_1") (pintype "passive"))
      (node (ref "R9") (pin "2") (pinfunction "2_2") (pintype "passive"))
      (node (ref "U5") (pin "6") (pinfunction "-IN_6") (pintype "input"))
    )
    (net (code "95") (name "Net-(U5B-OUT)") (class "Default")
      (node (ref "R14") (pin "2") (pinfunction "2_2") (pintype "passive"))
      (node (ref "R9") (pin "1") (pinfunction "1_1") (pintype "passive"))
      (node (ref "U5") (pin "7") (pinfunction "OUT_7") (pintype "output"))
    )
    (net (code "96") (name "Net-(U5C--IN)") (class "Default")
      (node (ref "R14") (pin "1") (pinfunction "1_1") (pintype "passive"))
      (node (ref "R15") (pin "2") (pinfunction "2_2") (pintype "passive"))
      (node (ref "U5") (pin "9") (pinfunction "-IN_9") (pintype "input"))
    )
    (net (code "97") (name "Net-(U5C-OUT)") (class "Default")
      (node (ref "R12") (pin "2") (pinfunction "2_2") (pintype "passive"))
      (node (ref "R15") (pin "1") (pinfunction "1_1") (pintype "passive"))
      (node (ref "U5") (pin "8") (pinfunction "OUT_8") (pintype "output"))
    )
    (net (code "98") (name "Net-(U5D--IN)") (class "Default")
      (node (ref "R16") (pin "1") (pinfunction "1_1") (pintype "passive"))
      (node (ref "R17") (pin "2") (pinfunction "2_2") (pintype "passive"))
      (node (ref "U5") (pin "13") (pinfunction "-IN_13") (pintype "input"))
    )
    (net (code "99") (name "Net-(U5D-OUT)") (class "Default")
      (node (ref "R13") (pin "2") (pinfunction "2_2") (pintype "passive"))
      (node (ref "R17") (pin "1") (pinfunction "1_1") (pintype "passive"))
      (node (ref "U5") (pin "14") (pinfunction "OUT_14") (pintype "output"))
    )
    (net (code "100") (name "Net-(U7A--IN)") (class "Default")
      (node (ref "C12") (pin "1") (pinfunction "1_1") (pintype "passive"))
      (node (ref "R110") (pin "2") (pinfunction "2_2") (pintype "passive"))
      (node (ref "R25") (pin "1") (pinfunction "1_1") (pintype "passive"))
      (node (ref "R26") (pin "2") (pinfunction "2_2") (pintype "passive"))
      (node (ref "R27") (pin "2") (pinfunction "2_2") (pintype "passive"))
      (node (ref "U7") (pin "2") (pinfunction "-IN_2") (pintype "input"))
    )
    (net (code "101") (name "Net-(U7B--IN)") (class "Default")
      (node (ref "C11") (pin "1") (pinfunction "1_1") (pintype "passive"))
      (node (ref "R109") (pin "2") (pinfunction "2_2") (pintype "passive"))
      (node (ref "R22") (pin "1") (pinfunction "1_1") (pintype "passive"))
      (node (ref "R23") (pin "2") (pinfunction "2_2") (pintype "passive"))
      (node (ref "R24") (pin "2") (pinfunction "2_2") (pintype "passive"))
      (node (ref "U7") (pin "6") (pinfunction "-IN_6") (pintype "input"))
    )
    (net (code "102") (name "Net-(U7C--IN)") (class "Default")
      (node (ref "C54") (pin "1") (pinfunction "1_1") (pintype "passive"))
      (node (ref "R105") (pin "1") (pinfunction "1_1") (pintype "passive"))
      (node (ref "R106") (pin "2") (pinfunction "2_2") (pintype "passive"))
      (node (ref "R107") (pin "2") (pinfunction "2_2") (pintype "passive"))
      (node (ref "R108") (pin "2") (pinfunction "2_2") (pintype "passive"))
      (node (ref "U7") (pin "9") (pinfunction "-IN_9") (pintype "input"))
    )
    (net (code "103") (name "Net-(U7D--IN)") (class "Default")
      (node (ref "C15") (pin "1") (pinfunction "1_1") (pintype "passive"))
      (node (ref "R111") (pin "2") (pinfunction "2_2") (pintype "passive"))
      (node (ref "R31") (pin "2") (pinfunction "2_2") (pintype "passive"))
      (node (ref "R32") (pin "2") (pinfunction "2_2") (pintype "passive"))
      (node (ref "R33") (pin "1") (pinfunction "1_1") (pintype "passive"))
      (node (ref "U7") (pin "13") (pinfunction "-IN_13") (pintype "input"))
    )
    (net (code "104") (name "Net-(U9-VFB)") (class "Default")
      (node (ref "R94") (pin "1") (pinfunction "1_1") (pintype "passive"))
      (node (ref "R95") (pin "1") (pinfunction "1_1") (pintype "passive"))
      (node (ref "U9") (pin "1") (pinfunction "VFB_1") (pintype "passive"))
    )
    (net (code "105") (name "Net-(U9-VIN_A)") (class "Default")
      (node (ref "C61") (pin "1") (pinfunction "1_1") (pintype "passive"))
      (node (ref "FB5") (pin "2") (pinfunction "2_2") (pintype "passive"))
      (node (ref "U9") (pin "4") (pinfunction "VIN_SW_4") (pintype "passive"))
      (node (ref "U9") (pin "5") (pinfunction "VIN_A_5") (pintype "passive"))
    )
    (net (code "106") (name "Net-(U11A--IN)") (class "Default")
      (node (ref "C52") (pin "1") (pinfunction "1_1") (pintype "passive"))
      (node (ref "R102") (pin "2") (pinfunction "2_2") (pintype "passive"))
      (node (ref "R99") (pin "1") (pinfunction "1_1") (pintype "passive"))
      (node (ref "U11") (pin "2") (pinfunction "-IN_2") (pintype "input"))
    )
    (net (code "107") (name "Net-(U11A-OUT)") (class "Default")
      (node (ref "C52") (pin "2") (pinfunction "2_2") (pintype "passive"))
      (node (ref "R101") (pin "1") (pinfunction "1_1") (pintype "passive"))
      (node (ref "R99") (pin "2") (pinfunction "2_2") (pintype "passive"))
      (node (ref "U11") (pin "1") (pinfunction "OUT_1") (pintype "output"))
    )
    (net (code "108") (name "Net-(U11B--IN)") (class "Default")
      (node (ref "C53") (pin "1") (pinfunction "1_1") (pintype "passive"))
      (node (ref "R100") (pin "1") (pinfunction "1_1") (pintype "passive"))
      (node (ref "R104") (pin "2") (pinfunction "2_2") (pintype "passive"))
      (node (ref "U11") (pin "6") (pinfunction "-IN_6") (pintype "input"))
    )
    (net (code "109") (name "Net-(U11B-OUT)") (class "Default")
      (node (ref "C53") (pin "2") (pinfunction "2_2") (pintype "passive"))
      (node (ref "R100") (pin "2") (pinfunction "2_2") (pintype "passive"))
      (node (ref "R103") (pin "1") (pinfunction "1_1") (pintype "passive"))
      (node (ref "U11") (pin "7") (pinfunction "OUT_7") (pintype "output"))
    )
    (net (code "110") (name "Net-(U11C--IN)") (class "Default")
      (node (ref "C26") (pin "1") (pinfunction "1_1") (pintype "passive"))
      (node (ref "R103") (pin "2") (pinfunction "2_2") (pintype "passive"))
      (node (ref "R71") (pin "1") (pinfunction "1_1") (pintype "passive"))
      (node (ref "U11") (pin "9") (pinfunction "-IN_9") (pintype "input"))
    )
    (net (code "111") (name "Net-(U11C-OUT)") (class "Default")
      (node (ref "C26") (pin "2") (pinfunction "2_2") (pintype "passive"))
      (node (ref "R71") (pin "2") (pinfunction "2_2") (pintype "passive"))
      (node (ref "R72") (pin "1") (pinfunction "1_1") (pintype "passive"))
      (node (ref "U11") (pin "8") (pinfunction "OUT_8") (pintype "output"))
    )
    (net (code "112") (name "Net-(U11D--IN)") (class "Default")
      (node (ref "C27") (pin "1") (pinfunction "1_1") (pintype "passive"))
      (node (ref "R101") (pin "2") (pinfunction "2_2") (pintype "passive"))
      (node (ref "R66") (pin "1") (pinfunction "1_1") (pintype "passive"))
      (node (ref "U11") (pin "13") (pinfunction "-IN_13") (pintype "input"))
    )
    (net (code "113") (name "Net-(U11D-OUT)") (class "Default")
      (node (ref "C27") (pin "2") (pinfunction "2_2") (pintype "passive"))
      (node (ref "R66") (pin "2") (pinfunction "2_2") (pintype "passive"))
      (node (ref "R67") (pin "1") (pinfunction "1_1") (pintype "passive"))
      (node (ref "U11") (pin "14") (pinfunction "OUT_14") (pintype "output"))
    )
    (net (code "114") (name "Net-(U13A--IN)") (class "Default")
      (node (ref "U13") (pin "1") (pinfunction "OUT_1") (pintype "output"))
      (node (ref "U13") (pin "2") (pinfunction "-IN_2") (pintype "input"))
    )
    (net (code "115") (name "Net-(U13B--IN)") (class "Default")
      (node (ref "R112") (pin "1") (pinfunction "1_1") (pintype "passive"))
      (node (ref "R113") (pin "2") (pinfunction "2_2") (pintype "passive"))
      (node (ref "U13") (pin "6") (pinfunction "-IN_6") (pintype "input"))
    )
    (net (code "116") (name "Net-(U13B-OUT)") (class "Default")
      (node (ref "R113") (pin "1") (pinfunction "1_1") (pintype "passive"))
      (node (ref "R114") (pin "2") (pinfunction "2_2") (pintype "passive"))
      (node (ref "U13") (pin "7") (pinfunction "OUT_7") (pintype "output"))
    )
    (net (code "117") (name "Net-(U13C--IN)") (class "Default")
      (node (ref "R114") (pin "1") (pinfunction "1_1") (pintype "passive"))
      (node (ref "R115") (pin "2") (pinfunction "2_2") (pintype "passive"))
      (node (ref "U13") (pin "9") (pinfunction "-IN_9") (pintype "input"))
    )
    (net (code "118") (name "Net-(U13C-OUT)") (class "Default")
      (node (ref "R115") (pin "1") (pinfunction "1_1") (pintype "passive"))
      (node (ref "R38") (pin "2") (pinfunction "2_2") (pintype "passive"))
      (node (ref "U13") (pin "8") (pinfunction "OUT_8") (pintype "output"))
    )
    (net (code "119") (name "Net-(U13D--IN)") (class "Default")
      (node (ref "U13") (pin "13") (pinfunction "-IN_13") (pintype "input"))
      (node (ref "U13") (pin "14") (pinfunction "OUT_14") (pintype "output"))
    )
    (net (code "120") (name "Net-(U14A--IN)") (class "Default")
      (node (ref "C6") (pin "1") (pinfunction "1_1") (pintype "passive"))
      (node (ref "R20") (pin "2") (pinfunction "2_2") (pintype "passive"))
      (node (ref "R43") (pin "1") (pinfunction "1_1") (pintype "passive"))
      (node (ref "U14") (pin "2") (pinfunction "-IN_2") (pintype "input"))
    )
    (net (code "121") (name "Net-(U14A-OUT)") (class "Default")
      (node (ref "C40") (pin "1") (pinfunction "1_1") (pintype "passive"))
      (node (ref "C6") (pin "2") (pinfunction "2_2") (pintype "passive"))
      (node (ref "R87") (pin "1") (pinfunction "1_1") (pintype "passive"))
      (node (ref "U14") (pin "1") (pinfunction "OUT_1") (pintype "output"))
    )
    (net (code "122") (name "Net-(U14B--IN)") (class "Default")
      (node (ref "C7") (pin "1") (pinfunction "1_1") (pintype "passive"))
      (node (ref "R40") (pin "2") (pinfunction "2_2") (pintype "passive"))
      (node (ref "R45") (pin "1") (pinfunction "1_1") (pintype "passive"))
      (node (ref "U14") (pin "6") (pinfunction "-IN_6") (pintype "input"))
    )
    (net (code "123") (name "Net-(U14B-OUT)") (class "Default")
      (node (ref "C41") (pin "1") (pinfunction "1_1") (pintype "passive"))
      (node (ref "C7") (pin "2") (pinfunction "2_2") (pintype "passive"))
      (node (ref "R88") (pin "1") (pinfunction "1_1") (pintype "passive"))
      (node (ref "U14") (pin "7") (pinfunction "OUT_7") (pintype "output"))
    )
    (net (code "124") (name "Net-(U14C--IN)") (class "Default")
      (node (ref "C18") (pin "1") (pinfunction "1_1") (pintype "passive"))
      (node (ref "R41") (pin "1") (pinfunction "1_1") (pintype "passive"))
      (node (ref "R44") (pin "2") (pinfunction "2_2") (pintype "passive"))
      (node (ref "U14") (pin "9") (pinfunction "-IN_9") (pintype "input"))
    )
    (net (code "125") (name "Net-(U14C-OUT)") (class "Default")
      (node (ref "C18") (pin "2") (pinfunction "2_2") (pintype "passive"))
      (node (ref "R41") (pin "2") (pinfunction "2_2") (pintype "passive"))
      (node (ref "R47") (pin "1") (pinfunction "1_1") (pintype "passive"))
      (node (ref "U14") (pin "8") (pinfunction "OUT_8") (pintype "output"))
    )
    (net (code "126") (name "Net-(U14D--IN)") (class "Default")
      (node (ref "C17") (pin "1") (pinfunction "1_1") (pintype "passive"))
      (node (ref "R39") (pin "1") (pinfunction "1_1") (pintype "passive"))
      (node (ref "R42") (pin "2") (pinfunction "2_2") (pintype "passive"))
      (node (ref "U14") (pin "13") (pinfunction "-IN_13") (pintype "input"))
    )
    (net (code "127") (name "Net-(U14D-OUT)") (class "Default")
      (node (ref "C17") (pin "2") (pinfunction "2_2") (pintype "passive"))
      (node (ref "R39") (pin "2") (pinfunction "2_2") (pintype "passive"))
      (node (ref "R46") (pin "1") (pinfunction "1_1") (pintype "passive"))
      (node (ref "U14") (pin "14") (pinfunction "OUT_14") (pintype "output"))
    )
    (net (code "128") (name "Net-(U15-A)") (class "Default")
      (node (ref "D5") (pin "C") (pinfunction "C_C") (pintype "passive"))
      (node (ref "R63") (pin "1") (pinfunction "1_1") (pintype "passive"))
      (node (ref "U15") (pin "1") (pinfunction "A_1") (pintype "bidirectional"))
    )
    (net (code "129") (name "Net-(U16A--IN)") (class "Default")
      (node (ref "C25") (pin "1") (pinfunction "1_1") (pintype "passive"))
      (node (ref "R52") (pin "1") (pinfunction "1_1") (pintype "passive"))
      (node (ref "R57") (pin "1") (pinfunction "1_1") (pintype "passive"))
      (node (ref "R96") (pin "1") (pinfunction "1_1") (pintype "passive"))
      (node (ref "U16") (pin "2") (pinfunction "-IN_2") (pintype "input"))
    )
    (net (code "130") (name "Net-(U16A-OUT)") (class "Default")
      (node (ref "C25") (pin "2") (pinfunction "2_2") (pintype "passive"))
      (node (ref "R52") (pin "2") (pinfunction "2_2") (pintype "passive"))
      (node (ref "R54") (pin "1") (pinfunction "1_1") (pintype "passive"))
      (node (ref "U16") (pin "1") (pinfunction "OUT_1") (pintype "output"))
    )
    (net (code "131") (name "Net-(U16B--IN)") (class "Default")
      (node (ref "C28") (pin "1") (pinfunction "1_1") (pintype "passive"))
      (node (ref "R53") (pin "1") (pinfunction "1_1") (pintype "passive"))
      (node (ref "R59") (pin "1") (pinfunction "1_1") (pintype "passive"))
      (node (ref "R97") (pin "1") (pinfunction "1_1") (pintype "passive"))
      (node (ref "U16") (pin "6") (pinfunction "-IN_6") (pintype "input"))
    )
    (net (code "132") (name "Net-(U16B-OUT)") (class "Default")
      (node (ref "C28") (pin "2") (pinfunction "2_2") (pintype "passive"))
      (node (ref "R53") (pin "2") (pinfunction "2_2") (pintype "passive"))
      (node (ref "R58") (pin "1") (pinfunction "1_1") (pintype "passive"))
      (node (ref "U16") (pin "7") (pinfunction "OUT_7") (pintype "output"))
    )
    (net (code "133") (name "Net-(U16C--IN)") (class "Default")
      (node (ref "C19") (pin "1") (pinfunction "1_1") (pintype "passive"))
      (node (ref "R50") (pin "1") (pinfunction "1_1") (pintype "passive"))
      (node (ref "R58") (pin "2") (pinfunction "2_2") (pintype "passive"))
      (node (ref "U16") (pin "9") (pinfunction "-IN_9") (pintype "input"))
    )
    (net (code "134") (name "Net-(U16C-OUT)") (class "Default")
      (node (ref "C19") (pin "2") (pinfunction "2_2") (pintype "passive"))
      (node (ref "R50") (pin "2") (pinfunction "2_2") (pintype "passive"))
      (node (ref "R51") (pin "1") (pinfunction "1_1") (pintype "passive"))
      (node (ref "U16") (pin "8") (pinfunction "OUT_8") (pintype "output"))
    )
    (net (code "135") (name "Net-(U16D--IN)") (class "Default")
      (node (ref "C24") (pin "1") (pinfunction "1_1") (pintype "passive"))
      (node (ref "R48") (pin "1") (pinfunction "1_1") (pintype "passive"))
      (node (ref "R54") (pin "2") (pinfunction "2_2") (pintype "passive"))
      (node (ref "U16") (pin "13") (pinfunction "-IN_13") (pintype "input"))
    )
    (net (code "136") (name "Net-(U16D-OUT)") (class "Default")
      (node (ref "C24") (pin "2") (pinfunction "2_2") (pintype "passive"))
      (node (ref "R48") (pin "2") (pinfunction "2_2") (pintype "passive"))
      (node (ref "R49") (pin "1") (pinfunction "1_1") (pintype "passive"))
      (node (ref "U16") (pin "14") (pinfunction "OUT_14") (pintype "output"))
    )
    (net (code "137") (name "OLED_CMD") (class "Default")
      (node (ref "U_DAISY") (pin "10") (pinfunction "GPIO9(SPI1_MISO)_10") (pintype "bidirectional"))
      (node (ref "U_DAISY") (pin "B10") (pinfunction "GPIO9(SPI1_MISO)_B10") (pintype "bidirectional"))
      (node (ref "U_OLED") (pin "6") (pinfunction "DC_6") (pintype "bidirectional"))
    )
    (net (code "138") (name "OLED_CS") (class "Default")
      (node (ref "U_DAISY") (pin "8") (pinfunction "GPIO7(SPI1_NSS)_8") (pintype "bidirectional"))
      (node (ref "U_DAISY") (pin "B8") (pinfunction "GPIO7(SPI1_NSS)_B8") (pintype "bidirectional"))
      (node (ref "U_OLED") (pin "7") (pinfunction "CS_7") (pintype "bidirectional"))
    )
    (net (code "139") (name "OLED_DATA") (class "Default")
      (node (ref "U_DAISY") (pin "11") (pinfunction "GPIO10(SPI1_MOSI)_11") (pintype "bidirectional"))
      (node (ref "U_DAISY") (pin "B11") (pinfunction "GPIO10(SPI1_MOSI)_B11") (pintype "bidirectional"))
      (node (ref "U_OLED") (pin "4") (pinfunction "SDA_4") (pintype "bidirectional"))
    )
    (net (code "140") (name "OLED_RST") (class "Default")
      (node (ref "U_DAISY") (pin "37") (pinfunction "GPIO30(USB_HS_D+)_37") (pintype "bidirectional"))
      (node (ref "U_DAISY") (pin "B37") (pinfunction "GPIO30(USB_HS_D+)_B37") (pintype "bidirectional"))
      (node (ref "U_OLED") (pin "5") (pinfunction "RES_5") (pintype "bidirectional"))
    )
    (net (code "141") (name "OLED_SCK") (class "Default")
      (node (ref "U_DAISY") (pin "9") (pinfunction "GPIO8(SPI1_SCK)_9") (pintype "bidirectional"))
      (node (ref "U_DAISY") (pin "B9") (pinfunction "GPIO8(SPI1_SCK)_B9") (pintype "bidirectional"))
      (node (ref "U_OLED") (pin "3") (pinfunction "SCL_3") (pintype "bidirectional"))
    )
    (net (code "142") (name "PCM3060_3V3") (class "Default")
      (node (ref "C2") (pin "1") (pinfunction "1_1") (pintype "passive"))
      (node (ref "C3") (pin "1") (pinfunction "1_1") (pintype "passive"))
      (node (ref "R19") (pin "1") (pinfunction "1_1") (pintype "passive"))
      (node (ref "U1") (pin "7") (pinfunction "VDD_7") (pintype "bidirectional"))
    )
    (net (code "143") (name "SAI2_FS_A") (class "Default")
      (node (ref "U1") (pin "11") (pinfunction "LRCK2_DAC_11") (pintype "bidirectional"))
      (node (ref "U1") (pin "4") (pinfunction "LRCK1_ADC_4") (pintype "bidirectional"))
      (node (ref "U_DAISY") (pin "34") (pinfunction "GPIO27(SAI2_FS_B)_34") (pintype "bidirectional"))
      (node (ref "U_DAISY") (pin "B34") (pinfunction "GPIO27(SAI2_FS_B)_B34") (pintype "bidirectional"))
    )
    (net (code "144") (name "SAI2_MCLK") (class "Default")
      (node (ref "U1") (pin "6") (pinfunction "SCK1_ADC_6") (pintype "bidirectional"))
      (node (ref "U1") (pin "9") (pinfunction "SCKI2_DAC_9") (pintype "bidirectional"))
      (node (ref "U_DAISY") (pin "31") (pinfunction "GPIO24(ADC9)_31") (pintype "bidirectional"))
      (node (ref "U_DAISY") (pin "B31") (pinfunction "GPIO24(ADC9)_B31") (pintype "bidirectional"))
    )
    (net (code "145") (name "SAI2_SCK_A") (class "Default")
      (node (ref "U1") (pin "10") (pinfunction "BCK2_DAC_10") (pintype "bidirectional"))
      (node (ref "U1") (pin "5") (pinfunction "BCK1_ADC_5") (pintype "bidirectional"))
      (node (ref "U_DAISY") (pin "35") (pinfunction "GPIO28(ADC11)_35") (pintype "bidirectional"))
      (node (ref "U_DAISY") (pin "B35") (pinfunction "GPIO28(ADC11)_B35") (pintype "bidirectional"))
    )
    (net (code "146") (name "SAI2_SD_A") (class "Default")
      (node (ref "U1") (pin "12") (pinfunction "DIN_DAC_12") (pintype "bidirectional"))
      (node (ref "U_DAISY") (pin "33") (pinfunction "GPIO26(SAI2_SD_A)_33") (pintype "bidirectional"))
      (node (ref "U_DAISY") (pin "B33") (pinfunction "GPIO26(SAI2_SD_A)_B33") (pintype "bidirectional"))
    )
    (net (code "147") (name "SAI2_SD_B") (class "Default")
      (node (ref "U1") (pin "3") (pinfunction "DOUT_ADC_3") (pintype "bidirectional"))
      (node (ref "U_DAISY") (pin "32") (pinfunction "GPIO25(ADC10)_32") (pintype "bidirectional"))
      (node (ref "U_DAISY") (pin "B32") (pinfunction "GPIO25(ADC10)_B32") (pintype "bidirectional"))
    )
    (net (code "148") (name "SD_CK") (class "Default")
      (node (ref "U3") (pin "P$5") (pinfunction "SCK_P$5") (pintype "bidirectional"))
      (node (ref "U_DAISY") (pin "7") (pinfunction "GPIO6(SDMMC1_CK)_7") (pintype "bidirectional"))
      (node (ref "U_DAISY") (pin "B7") (pinfunction "GPIO6(SDMMC1_CK)_B7") (pintype "bidirectional"))
    )
    (net (code "149") (name "SD_CMD") (class "Default")
      (node (ref "R5") (pin "1") (pinfunction "1_1") (pintype "passive"))
      (node (ref "U3") (pin "P$3") (pinfunction "CMD/DI_P$3") (pintype "bidirectional"))
      (node (ref "U_DAISY") (pin "6") (pinfunction "GPIO5(SDMMC1_CMD)_6") (pintype "bidirectional"))
      (node (ref "U_DAISY") (pin "B6") (pinfunction "GPIO5(SDMMC1_CMD)_B6") (pintype "bidirectional"))
    )
    (net (code "150") (name "SD_D0") (class "Default")
      (node (ref "R6") (pin "1") (pinfunction "1_1") (pintype "passive"))
      (node (ref "U3") (pin "P$7") (pinfunction "D0/DO_P$7") (pintype "bidirectional"))
      (node (ref "U_DAISY") (pin "5") (pinfunction "GPIO4(SDMMC1_D0)_5") (pintype "bidirectional"))
      (node (ref "U_DAISY") (pin "B5") (pinfunction "GPIO4(SDMMC1_D0)_B5") (pintype "bidirectional"))
    )
    (net (code "151") (name "SD_D1") (class "Default")
      (node (ref "R7") (pin "1") (pinfunction "1_1") (pintype "passive"))
      (node (ref "U3") (pin "P$8") (pinfunction "D1/RSV_P$8") (pintype "bidirectional"))
      (node (ref "U_DAISY") (pin "4") (pinfunction "GPIO3(SDMMC1_D1)_4") (pintype "bidirectional"))
      (node (ref "U_DAISY") (pin "B4") (pinfunction "GPIO3(SDMMC1_D1)_B4") (pintype "bidirectional"))
    )
    (net (code "152") (name "SD_D2") (class "Default")
      (node (ref "R3") (pin "1") (pinfunction "1_1") (pintype "passive"))
      (node (ref "U3") (pin "P$1") (pinfunction "D2/NC_P$1") (pintype "bidirectional"))
      (node (ref "U_DAISY") (pin "3") (pinfunction "GPIO2(SDMMC1_D2)_3") (pintype "bidirectional"))
      (node (ref "U_DAISY") (pin "B3") (pinfunction "GPIO2(SDMMC1_D2)_B3") (pintype "bidirectional"))
    )
    (net (code "153") (name "SD_D3") (class "Default")
      (node (ref "R4") (pin "1") (pinfunction "1_1") (pintype "passive"))
      (node (ref "U3") (pin "P$2") (pinfunction "D3/CS_P$2") (pintype "bidirectional"))
      (node (ref "U_DAISY") (pin "2") (pinfunction "GPIO1(SDMMC1_D3)_2") (pintype "bidirectional"))
      (node (ref "U_DAISY") (pin "B2") (pinfunction "GPIO1(SDMMC1_D3)_B2") (pintype "bidirectional"))
    )
    (net (code "154") (name "SPI1_MOSI_IN") (class "Default")
      (node (ref "J_GATE_IN_1") (pin "3") (pinfunction "TIP_3") (pintype "passive"))
      (node (ref "R21") (pin "1") (pinfunction "1_1") (pintype "passive"))
    )
    (net (code "155") (name "SPI1_NSS_OUT") (class "Default")
      (node (ref "J_GATE_OUT") (pin "3") (pinfunction "TIP_3") (pintype "passive"))
      (node (ref "R38") (pin "1") (pinfunction "1_1") (pintype "passive"))
    )
    (net (code "156") (name "USART1_RX") (class "Default")
      (node (ref "R64") (pin "2") (pinfunction "2_2") (pintype "passive"))
      (node (ref "U15") (pin "4") (pinfunction "OUT_4") (pintype "bidirectional"))
      (node (ref "U_DAISY") (pin "15") (pinfunction "GPIO14(USART1_RX)_15") (pintype "bidirectional"))
      (node (ref "U_DAISY") (pin "B15") (pinfunction "GPIO14(USART1_RX)_B15") (pintype "bidirectional"))
    )
    (net (code "157") (name "USART1_TX") (class "Default")
      (node (ref "R2") (pin "2") (pinfunction "2_2") (pintype "passive"))
      (node (ref "U_DAISY") (pin "14") (pinfunction "GPIO13(USART1_TX)_14") (pintype "bidirectional"))
      (node (ref "U_DAISY") (pin "B14") (pinfunction "GPIO13(USART1_TX)_B14") (pintype "bidirectional"))
    )
    (net (code "158") (name "unconnected-(J_AUDIO_IN_1-NORM-Pad2)") (class "Default")
      (node (ref "J_AUDIO_IN_1") (pin "2") (pinfunction "NORM_2") (pintype "passive"))
    )
    (net (code "159") (name "unconnected-(J_AUDIO_OUT_1-NORM-Pad2)") (class "Default")
      (node (ref "J_AUDIO_OUT_1") (pin "2") (pinfunction "NORM_2") (pintype "passive"))
    )
    (net (code "160") (name "unconnected-(J_AUDIO_OUT_2-NORM-Pad2)") (class "Default")
      (node (ref "J_AUDIO_OUT_2") (pin "2") (pinfunction "NORM_2") (pintype "passive"))
    )
    (net (code "161") (name "unconnected-(J_AUDIO_OUT_3-NORM-Pad2)") (class "Default")
      (node (ref "J_AUDIO_OUT_3") (pin "2") (pinfunction "NORM_2") (pintype "passive"))
    )
    (net (code "162") (name "unconnected-(J_AUDIO_OUT_4-NORM-Pad2)") (class "Default")
      (node (ref "J_AUDIO_OUT_4") (pin "2") (pinfunction "NORM_2") (pintype "passive"))
    )
    (net (code "163") (name "unconnected-(J_CV_1-NORM-Pad2)") (class "Default")
      (node (ref "J_CV_1") (pin "2") (pinfunction "NORM_2") (pintype "passive"))
    )
    (net (code "164") (name "unconnected-(J_CV_2-NORM-Pad2)") (class "Default")
      (node (ref "J_CV_2") (pin "2") (pinfunction "NORM_2") (pintype "passive"))
    )
    (net (code "165") (name "unconnected-(J_CV_3-NORM-Pad2)") (class "Default")
      (node (ref "J_CV_3") (pin "2") (pinfunction "NORM_2") (pintype "passive"))
    )
    (net (code "166") (name "unconnected-(J_CV_4-NORM-Pad2)") (class "Default")
      (node (ref "J_CV_4") (pin "2") (pinfunction "NORM_2") (pintype "passive"))
    )
    (net (code "167") (name "unconnected-(J_CV_OUT_1-NORM-Pad2)") (class "Default")
      (node (ref "J_CV_OUT_1") (pin "2") (pinfunction "NORM_2") (pintype "passive"))
    )
    (net (code "168") (name "unconnected-(J_CV_OUT_2-NORM-Pad2)") (class "Default")
      (node (ref "J_CV_OUT_2") (pin "2") (pinfunction "NORM_2") (pintype "passive"))
    )
    (net (code "169") (name "unconnected-(J_GATE_IN_1-NORM-Pad2)") (class "Default")
      (node (ref "J_GATE_IN_1") (pin "2") (pinfunction "NORM_2") (pintype "passive"))
    )
    (net (code "170") (name "unconnected-(J_GATE_IN_2-NORM-Pad2)") (class "Default")
      (node (ref "J_GATE_IN_2") (pin "2") (pinfunction "NORM_2") (pintype "passive"))
    )
    (net (code "171") (name "unconnected-(J_GATE_OUT-NORM-Pad2)") (class "Default")
      (node (ref "J_GATE_OUT") (pin "2") (pinfunction "NORM_2") (pintype "passive"))
    )
    (net (code "172") (name "unconnected-(U1-VOUTL--Pad19)") (class "Default")
      (node (ref "U1") (pin "19") (pinfunction "VOUTL-_19") (pintype "bidirectional"))
    )
    (net (code "173") (name "unconnected-(U1-VOUTR--Pad17)") (class "Default")
      (node (ref "U1") (pin "17") (pinfunction "VOUTR-_17") (pintype "bidirectional"))
    )
    (net (code "174") (name "unconnected-(U1-ZEROL-Pad14)") (class "Default")
      (node (ref "U1") (pin "14") (pinfunction "ZEROL_14") (pintype "bidirectional"))
    )
    (net (code "175") (name "unconnected-(U1-ZEROR-Pad13)") (class "Default")
      (node (ref "U1") (pin "13") (pinfunction "ZEROR_13") (pintype "bidirectional"))
    )
    (net (code "176") (name "unconnected-(U9-N.C.-Pad6)") (class "Default")
      (node (ref "U9") (pin "6") (pinfunction "N.C._6") (pintype "no_connect"))
    )
  )
)
